# DBS.net
KiCad netlist of a schematic drawn in EAGLE
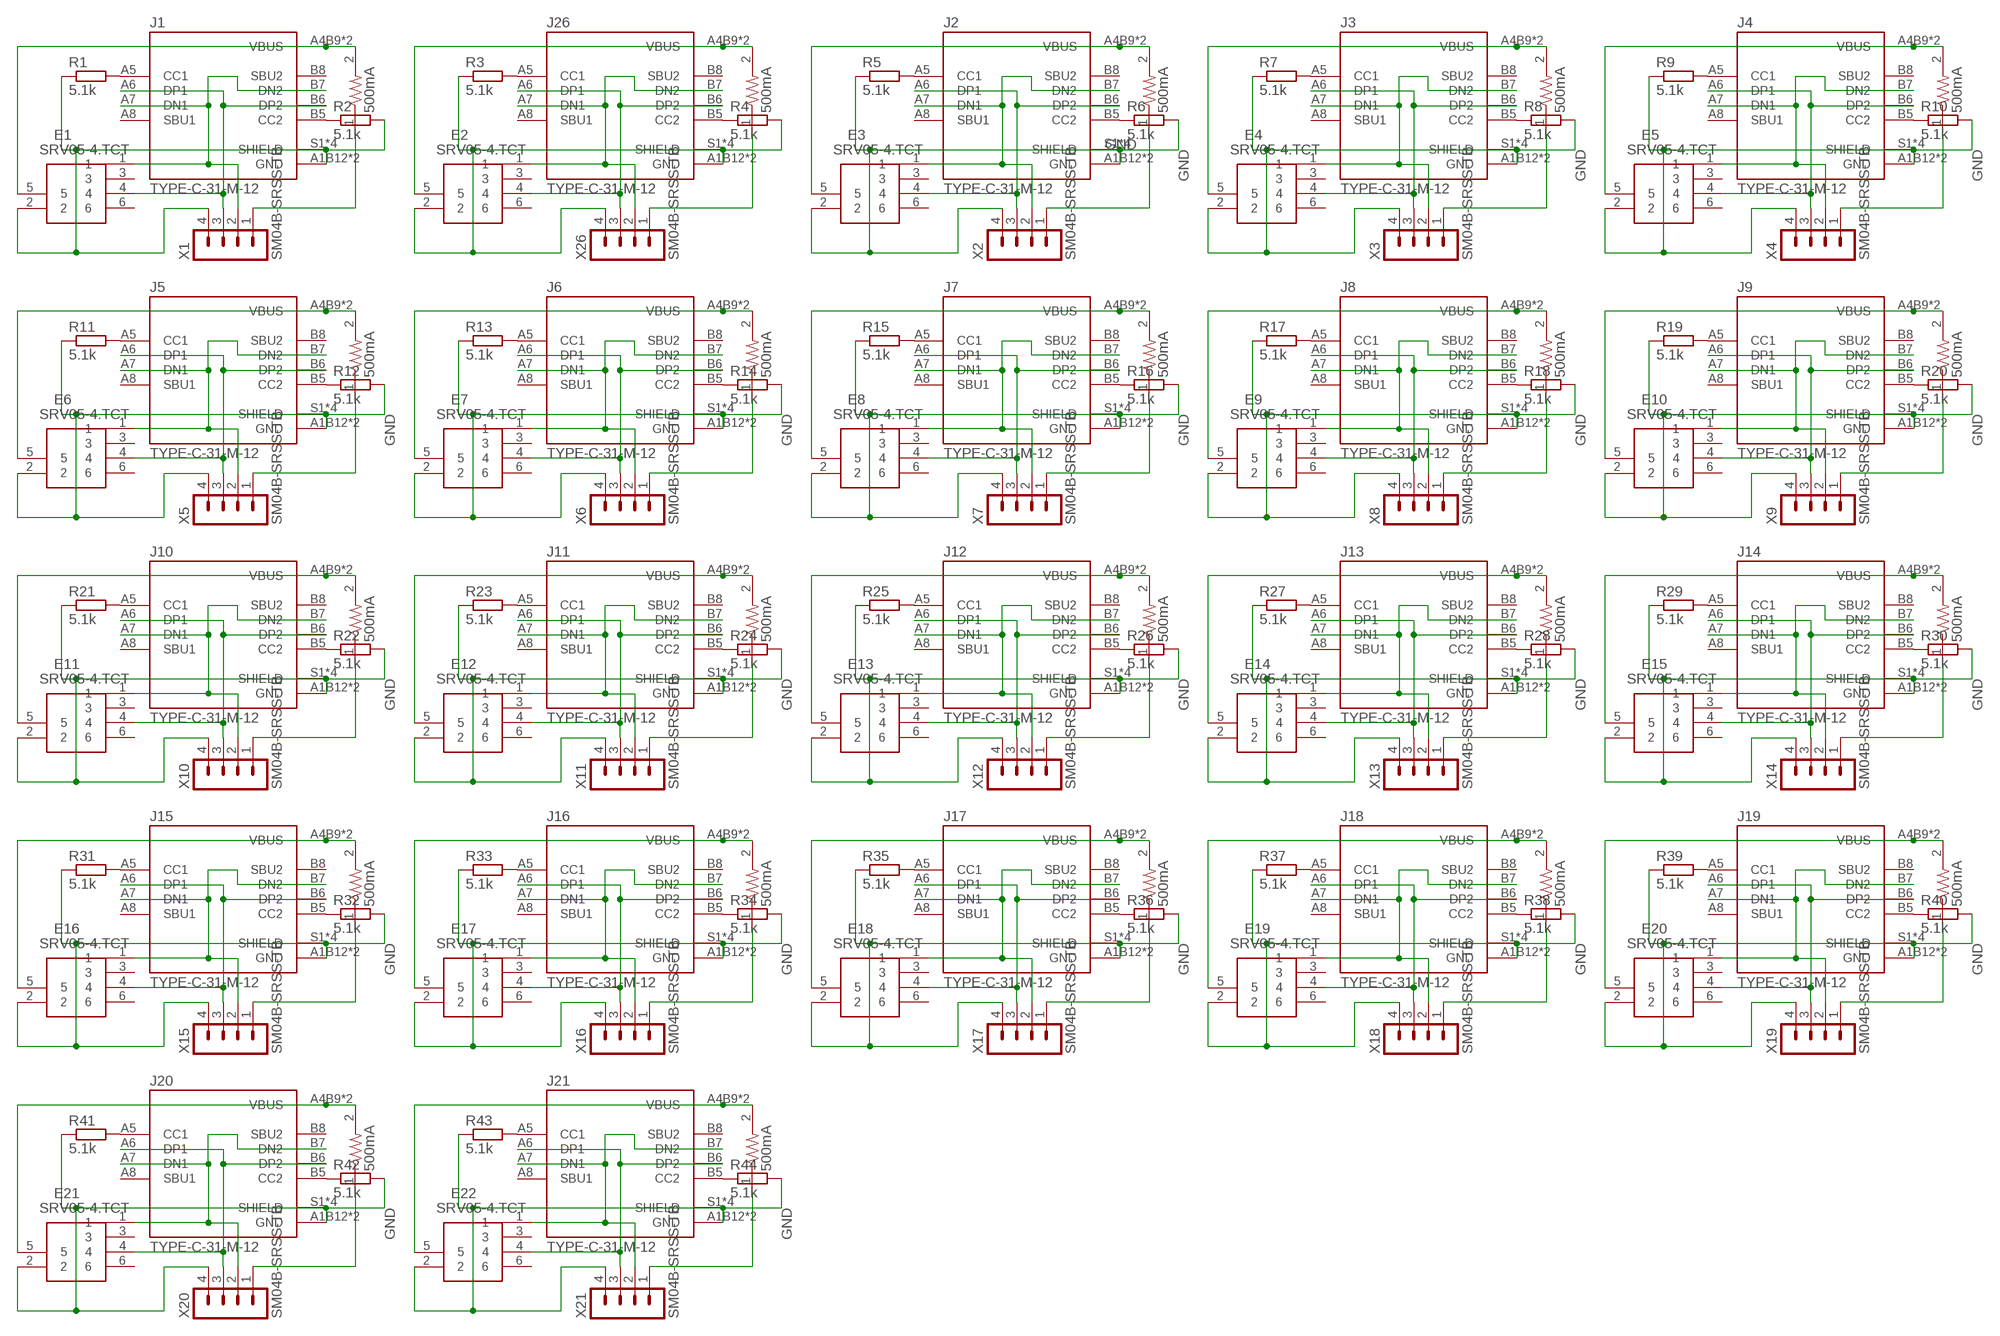
[diagram p0: schematic, sheet 1]

(export (version "E")
  (design (tool "Eeschema 10.0.6"))
  (components
    (comp (ref "E1")
      (value "SRV05-4.TCT")
      (footprint "eagle-import:SOT95P280X145-6N")
      (fields (field (name "MF") "Semtech") (field (name "MP") "SRV05-4.TC"))
      (libsource (lib "eagle-import") (part "SRV05-4.TCT"))
    )
    (comp (ref "E2")
      (value "SRV05-4.TCT")
      (footprint "eagle-import:SOT95P280X145-6N")
      (fields (field (name "MF") "Semtech") (field (name "MP") "SRV05-4.TC"))
      (libsource (lib "eagle-import") (part "SRV05-4.TCT"))
    )
    (comp (ref "E3")
      (value "SRV05-4.TCT")
      (footprint "eagle-import:SOT95P280X145-6N")
      (fields (field (name "MF") "Semtech") (field (name "MP") "SRV05-4.TC"))
      (libsource (lib "eagle-import") (part "SRV05-4.TCT"))
    )
    (comp (ref "E4")
      (value "SRV05-4.TCT")
      (footprint "eagle-import:SOT95P280X145-6N")
      (fields (field (name "MF") "Semtech") (field (name "MP") "SRV05-4.TC"))
      (libsource (lib "eagle-import") (part "SRV05-4.TCT"))
    )
    (comp (ref "E5")
      (value "SRV05-4.TCT")
      (footprint "eagle-import:SOT95P280X145-6N")
      (fields (field (name "MF") "Semtech") (field (name "MP") "SRV05-4.TC"))
      (libsource (lib "eagle-import") (part "SRV05-4.TCT"))
    )
    (comp (ref "E6")
      (value "SRV05-4.TCT")
      (footprint "eagle-import:SOT95P280X145-6N")
      (fields (field (name "MF") "Semtech") (field (name "MP") "SRV05-4.TC"))
      (libsource (lib "eagle-import") (part "SRV05-4.TCT"))
    )
    (comp (ref "E7")
      (value "SRV05-4.TCT")
      (footprint "eagle-import:SOT95P280X145-6N")
      (fields (field (name "MF") "Semtech") (field (name "MP") "SRV05-4.TC"))
      (libsource (lib "eagle-import") (part "SRV05-4.TCT"))
    )
    (comp (ref "E8")
      (value "SRV05-4.TCT")
      (footprint "eagle-import:SOT95P280X145-6N")
      (fields (field (name "MF") "Semtech") (field (name "MP") "SRV05-4.TC"))
      (libsource (lib "eagle-import") (part "SRV05-4.TCT"))
    )
    (comp (ref "E9")
      (value "SRV05-4.TCT")
      (footprint "eagle-import:SOT95P280X145-6N")
      (fields (field (name "MF") "Semtech") (field (name "MP") "SRV05-4.TC"))
      (libsource (lib "eagle-import") (part "SRV05-4.TCT"))
    )
    (comp (ref "E10")
      (value "SRV05-4.TCT")
      (footprint "eagle-import:SOT95P280X145-6N")
      (fields (field (name "MF") "Semtech") (field (name "MP") "SRV05-4.TC"))
      (libsource (lib "eagle-import") (part "SRV05-4.TCT"))
    )
    (comp (ref "E11")
      (value "SRV05-4.TCT")
      (footprint "eagle-import:SOT95P280X145-6N")
      (fields (field (name "MF") "Semtech") (field (name "MP") "SRV05-4.TC"))
      (libsource (lib "eagle-import") (part "SRV05-4.TCT"))
    )
    (comp (ref "E12")
      (value "SRV05-4.TCT")
      (footprint "eagle-import:SOT95P280X145-6N")
      (fields (field (name "MF") "Semtech") (field (name "MP") "SRV05-4.TC"))
      (libsource (lib "eagle-import") (part "SRV05-4.TCT"))
    )
    (comp (ref "E13")
      (value "SRV05-4.TCT")
      (footprint "eagle-import:SOT95P280X145-6N")
      (fields (field (name "MF") "Semtech") (field (name "MP") "SRV05-4.TC"))
      (libsource (lib "eagle-import") (part "SRV05-4.TCT"))
    )
    (comp (ref "E14")
      (value "SRV05-4.TCT")
      (footprint "eagle-import:SOT95P280X145-6N")
      (fields (field (name "MF") "Semtech") (field (name "MP") "SRV05-4.TC"))
      (libsource (lib "eagle-import") (part "SRV05-4.TCT"))
    )
    (comp (ref "E15")
      (value "SRV05-4.TCT")
      (footprint "eagle-import:SOT95P280X145-6N")
      (fields (field (name "MF") "Semtech") (field (name "MP") "SRV05-4.TC"))
      (libsource (lib "eagle-import") (part "SRV05-4.TCT"))
    )
    (comp (ref "E16")
      (value "SRV05-4.TCT")
      (footprint "eagle-import:SOT95P280X145-6N")
      (fields (field (name "MF") "Semtech") (field (name "MP") "SRV05-4.TC"))
      (libsource (lib "eagle-import") (part "SRV05-4.TCT"))
    )
    (comp (ref "E17")
      (value "SRV05-4.TCT")
      (footprint "eagle-import:SOT95P280X145-6N")
      (fields (field (name "MF") "Semtech") (field (name "MP") "SRV05-4.TC"))
      (libsource (lib "eagle-import") (part "SRV05-4.TCT"))
    )
    (comp (ref "E18")
      (value "SRV05-4.TCT")
      (footprint "eagle-import:SOT95P280X145-6N")
      (fields (field (name "MF") "Semtech") (field (name "MP") "SRV05-4.TC"))
      (libsource (lib "eagle-import") (part "SRV05-4.TCT"))
    )
    (comp (ref "E19")
      (value "SRV05-4.TCT")
      (footprint "eagle-import:SOT95P280X145-6N")
      (fields (field (name "MF") "Semtech") (field (name "MP") "SRV05-4.TC"))
      (libsource (lib "eagle-import") (part "SRV05-4.TCT"))
    )
    (comp (ref "E20")
      (value "SRV05-4.TCT")
      (footprint "eagle-import:SOT95P280X145-6N")
      (fields (field (name "MF") "Semtech") (field (name "MP") "SRV05-4.TC"))
      (libsource (lib "eagle-import") (part "SRV05-4.TCT"))
    )
    (comp (ref "E21")
      (value "SRV05-4.TCT")
      (footprint "eagle-import:SOT95P280X145-6N")
      (fields (field (name "MF") "Semtech") (field (name "MP") "SRV05-4.TC"))
      (libsource (lib "eagle-import") (part "SRV05-4.TCT"))
    )
    (comp (ref "E22")
      (value "SRV05-4.TCT")
      (footprint "eagle-import:SOT95P280X145-6N")
      (fields (field (name "MF") "Semtech") (field (name "MP") "SRV05-4.TC"))
      (libsource (lib "eagle-import") (part "SRV05-4.TCT"))
    )
    (comp (ref "F1")
      (value "500mA")
      (footprint "eagle-import:RESC3216X125N")
      (fields (field (name "MF") "Bel Fuse") (field (name "MP") "0ZCJ0075AF2E"))
      (libsource (lib "eagle-import") (part "0ZCJ0075AF2E"))
    )
    (comp (ref "F2")
      (value "500mA")
      (footprint "eagle-import:RESC3216X125N")
      (fields (field (name "MF") "Bel Fuse") (field (name "MP") "0ZCJ0075AF2E"))
      (libsource (lib "eagle-import") (part "0ZCJ0075AF2E"))
    )
    (comp (ref "F3")
      (value "500mA")
      (footprint "eagle-import:RESC3216X125N")
      (fields (field (name "MF") "Bel Fuse") (field (name "MP") "0ZCJ0075AF2E"))
      (libsource (lib "eagle-import") (part "0ZCJ0075AF2E"))
    )
    (comp (ref "F4")
      (value "500mA")
      (footprint "eagle-import:RESC3216X125N")
      (fields (field (name "MF") "Bel Fuse") (field (name "MP") "0ZCJ0075AF2E"))
      (libsource (lib "eagle-import") (part "0ZCJ0075AF2E"))
    )
    (comp (ref "F5")
      (value "500mA")
      (footprint "eagle-import:RESC3216X125N")
      (fields (field (name "MF") "Bel Fuse") (field (name "MP") "0ZCJ0075AF2E"))
      (libsource (lib "eagle-import") (part "0ZCJ0075AF2E"))
    )
    (comp (ref "F6")
      (value "500mA")
      (footprint "eagle-import:RESC3216X125N")
      (fields (field (name "MF") "Bel Fuse") (field (name "MP") "0ZCJ0075AF2E"))
      (libsource (lib "eagle-import") (part "0ZCJ0075AF2E"))
    )
    (comp (ref "F7")
      (value "500mA")
      (footprint "eagle-import:RESC3216X125N")
      (fields (field (name "MF") "Bel Fuse") (field (name "MP") "0ZCJ0075AF2E"))
      (libsource (lib "eagle-import") (part "0ZCJ0075AF2E"))
    )
    (comp (ref "F8")
      (value "500mA")
      (footprint "eagle-import:RESC3216X125N")
      (fields (field (name "MF") "Bel Fuse") (field (name "MP") "0ZCJ0075AF2E"))
      (libsource (lib "eagle-import") (part "0ZCJ0075AF2E"))
    )
    (comp (ref "F9")
      (value "500mA")
      (footprint "eagle-import:RESC3216X125N")
      (fields (field (name "MF") "Bel Fuse") (field (name "MP") "0ZCJ0075AF2E"))
      (libsource (lib "eagle-import") (part "0ZCJ0075AF2E"))
    )
    (comp (ref "F10")
      (value "500mA")
      (footprint "eagle-import:RESC3216X125N")
      (fields (field (name "MF") "Bel Fuse") (field (name "MP") "0ZCJ0075AF2E"))
      (libsource (lib "eagle-import") (part "0ZCJ0075AF2E"))
    )
    (comp (ref "F11")
      (value "500mA")
      (footprint "eagle-import:RESC3216X125N")
      (fields (field (name "MF") "Bel Fuse") (field (name "MP") "0ZCJ0075AF2E"))
      (libsource (lib "eagle-import") (part "0ZCJ0075AF2E"))
    )
    (comp (ref "F12")
      (value "500mA")
      (footprint "eagle-import:RESC3216X125N")
      (fields (field (name "MF") "Bel Fuse") (field (name "MP") "0ZCJ0075AF2E"))
      (libsource (lib "eagle-import") (part "0ZCJ0075AF2E"))
    )
    (comp (ref "F13")
      (value "500mA")
      (footprint "eagle-import:RESC3216X125N")
      (fields (field (name "MF") "Bel Fuse") (field (name "MP") "0ZCJ0075AF2E"))
      (libsource (lib "eagle-import") (part "0ZCJ0075AF2E"))
    )
    (comp (ref "F14")
      (value "500mA")
      (footprint "eagle-import:RESC3216X125N")
      (fields (field (name "MF") "Bel Fuse") (field (name "MP") "0ZCJ0075AF2E"))
      (libsource (lib "eagle-import") (part "0ZCJ0075AF2E"))
    )
    (comp (ref "F15")
      (value "500mA")
      (footprint "eagle-import:RESC3216X125N")
      (fields (field (name "MF") "Bel Fuse") (field (name "MP") "0ZCJ0075AF2E"))
      (libsource (lib "eagle-import") (part "0ZCJ0075AF2E"))
    )
    (comp (ref "F16")
      (value "500mA")
      (footprint "eagle-import:RESC3216X125N")
      (fields (field (name "MF") "Bel Fuse") (field (name "MP") "0ZCJ0075AF2E"))
      (libsource (lib "eagle-import") (part "0ZCJ0075AF2E"))
    )
    (comp (ref "F17")
      (value "500mA")
      (footprint "eagle-import:RESC3216X125N")
      (fields (field (name "MF") "Bel Fuse") (field (name "MP") "0ZCJ0075AF2E"))
      (libsource (lib "eagle-import") (part "0ZCJ0075AF2E"))
    )
    (comp (ref "F18")
      (value "500mA")
      (footprint "eagle-import:RESC3216X125N")
      (fields (field (name "MF") "Bel Fuse") (field (name "MP") "0ZCJ0075AF2E"))
      (libsource (lib "eagle-import") (part "0ZCJ0075AF2E"))
    )
    (comp (ref "F19")
      (value "500mA")
      (footprint "eagle-import:RESC3216X125N")
      (fields (field (name "MF") "Bel Fuse") (field (name "MP") "0ZCJ0075AF2E"))
      (libsource (lib "eagle-import") (part "0ZCJ0075AF2E"))
    )
    (comp (ref "F20")
      (value "500mA")
      (footprint "eagle-import:RESC3216X125N")
      (fields (field (name "MF") "Bel Fuse") (field (name "MP") "0ZCJ0075AF2E"))
      (libsource (lib "eagle-import") (part "0ZCJ0075AF2E"))
    )
    (comp (ref "F21")
      (value "500mA")
      (footprint "eagle-import:RESC3216X125N")
      (fields (field (name "MF") "Bel Fuse") (field (name "MP") "0ZCJ0075AF2E"))
      (libsource (lib "eagle-import") (part "0ZCJ0075AF2E"))
    )
    (comp (ref "F22")
      (value "500mA")
      (footprint "eagle-import:RESC3216X125N")
      (fields (field (name "MF") "Bel Fuse") (field (name "MP") "0ZCJ0075AF2E"))
      (libsource (lib "eagle-import") (part "0ZCJ0075AF2E"))
    )
    (comp (ref "J1")
      (value "TYPE-C-31-M-12")
      (footprint "eagle-import:HRO_TYPE-C-31-M-12")
      (fields (field (name "MF") "HRO Electronics Co., Ltd."))
      (libsource (lib "eagle-import") (part "TYPE-C-31-M-12"))
    )
    (comp (ref "J2")
      (value "TYPE-C-31-M-12")
      (footprint "eagle-import:HRO_TYPE-C-31-M-12")
      (fields (field (name "MF") "HRO Electronics Co., Ltd."))
      (libsource (lib "eagle-import") (part "TYPE-C-31-M-12"))
    )
    (comp (ref "J3")
      (value "TYPE-C-31-M-12")
      (footprint "eagle-import:HRO_TYPE-C-31-M-12")
      (fields (field (name "MF") "HRO Electronics Co., Ltd."))
      (libsource (lib "eagle-import") (part "TYPE-C-31-M-12"))
    )
    (comp (ref "J4")
      (value "TYPE-C-31-M-12")
      (footprint "eagle-import:HRO_TYPE-C-31-M-12")
      (fields (field (name "MF") "HRO Electronics Co., Ltd."))
      (libsource (lib "eagle-import") (part "TYPE-C-31-M-12"))
    )
    (comp (ref "J5")
      (value "TYPE-C-31-M-12")
      (footprint "eagle-import:HRO_TYPE-C-31-M-12")
      (fields (field (name "MF") "HRO Electronics Co., Ltd."))
      (libsource (lib "eagle-import") (part "TYPE-C-31-M-12"))
    )
    (comp (ref "J6")
      (value "TYPE-C-31-M-12")
      (footprint "eagle-import:HRO_TYPE-C-31-M-12")
      (fields (field (name "MF") "HRO Electronics Co., Ltd."))
      (libsource (lib "eagle-import") (part "TYPE-C-31-M-12"))
    )
    (comp (ref "J7")
      (value "TYPE-C-31-M-12")
      (footprint "eagle-import:HRO_TYPE-C-31-M-12")
      (fields (field (name "MF") "HRO Electronics Co., Ltd."))
      (libsource (lib "eagle-import") (part "TYPE-C-31-M-12"))
    )
    (comp (ref "J8")
      (value "TYPE-C-31-M-12")
      (footprint "eagle-import:HRO_TYPE-C-31-M-12")
      (fields (field (name "MF") "HRO Electronics Co., Ltd."))
      (libsource (lib "eagle-import") (part "TYPE-C-31-M-12"))
    )
    (comp (ref "J9")
      (value "TYPE-C-31-M-12")
      (footprint "eagle-import:HRO_TYPE-C-31-M-12")
      (fields (field (name "MF") "HRO Electronics Co., Ltd."))
      (libsource (lib "eagle-import") (part "TYPE-C-31-M-12"))
    )
    (comp (ref "J10")
      (value "TYPE-C-31-M-12")
      (footprint "eagle-import:HRO_TYPE-C-31-M-12")
      (fields (field (name "MF") "HRO Electronics Co., Ltd."))
      (libsource (lib "eagle-import") (part "TYPE-C-31-M-12"))
    )
    (comp (ref "J11")
      (value "TYPE-C-31-M-12")
      (footprint "eagle-import:HRO_TYPE-C-31-M-12")
      (fields (field (name "MF") "HRO Electronics Co., Ltd."))
      (libsource (lib "eagle-import") (part "TYPE-C-31-M-12"))
    )
    (comp (ref "J12")
      (value "TYPE-C-31-M-12")
      (footprint "eagle-import:HRO_TYPE-C-31-M-12")
      (fields (field (name "MF") "HRO Electronics Co., Ltd."))
      (libsource (lib "eagle-import") (part "TYPE-C-31-M-12"))
    )
    (comp (ref "J13")
      (value "TYPE-C-31-M-12")
      (footprint "eagle-import:HRO_TYPE-C-31-M-12")
      (fields (field (name "MF") "HRO Electronics Co., Ltd."))
      (libsource (lib "eagle-import") (part "TYPE-C-31-M-12"))
    )
    (comp (ref "J14")
      (value "TYPE-C-31-M-12")
      (footprint "eagle-import:HRO_TYPE-C-31-M-12")
      (fields (field (name "MF") "HRO Electronics Co., Ltd."))
      (libsource (lib "eagle-import") (part "TYPE-C-31-M-12"))
    )
    (comp (ref "J15")
      (value "TYPE-C-31-M-12")
      (footprint "eagle-import:HRO_TYPE-C-31-M-12")
      (fields (field (name "MF") "HRO Electronics Co., Ltd."))
      (libsource (lib "eagle-import") (part "TYPE-C-31-M-12"))
    )
    (comp (ref "J16")
      (value "TYPE-C-31-M-12")
      (footprint "eagle-import:HRO_TYPE-C-31-M-12")
      (fields (field (name "MF") "HRO Electronics Co., Ltd."))
      (libsource (lib "eagle-import") (part "TYPE-C-31-M-12"))
    )
    (comp (ref "J17")
      (value "TYPE-C-31-M-12")
      (footprint "eagle-import:HRO_TYPE-C-31-M-12")
      (fields (field (name "MF") "HRO Electronics Co., Ltd."))
      (libsource (lib "eagle-import") (part "TYPE-C-31-M-12"))
    )
    (comp (ref "J18")
      (value "TYPE-C-31-M-12")
      (footprint "eagle-import:HRO_TYPE-C-31-M-12")
      (fields (field (name "MF") "HRO Electronics Co., Ltd."))
      (libsource (lib "eagle-import") (part "TYPE-C-31-M-12"))
    )
    (comp (ref "J19")
      (value "TYPE-C-31-M-12")
      (footprint "eagle-import:HRO_TYPE-C-31-M-12")
      (fields (field (name "MF") "HRO Electronics Co., Ltd."))
      (libsource (lib "eagle-import") (part "TYPE-C-31-M-12"))
    )
    (comp (ref "J20")
      (value "TYPE-C-31-M-12")
      (footprint "eagle-import:HRO_TYPE-C-31-M-12")
      (fields (field (name "MF") "HRO Electronics Co., Ltd."))
      (libsource (lib "eagle-import") (part "TYPE-C-31-M-12"))
    )
    (comp (ref "J21")
      (value "TYPE-C-31-M-12")
      (footprint "eagle-import:HRO_TYPE-C-31-M-12")
      (fields (field (name "MF") "HRO Electronics Co., Ltd."))
      (libsource (lib "eagle-import") (part "TYPE-C-31-M-12"))
    )
    (comp (ref "J26")
      (value "TYPE-C-31-M-12")
      (footprint "eagle-import:HRO_TYPE-C-31-M-12")
      (fields (field (name "MF") "HRO Electronics Co., Ltd."))
      (libsource (lib "eagle-import") (part "TYPE-C-31-M-12"))
    )
    (comp (ref "R1")
      (value "5.1k")
      (footprint "eagle-import:R0603")
      (libsource (lib "eagle-import") (part "RESISTOR-0603"))
    )
    (comp (ref "R2")
      (value "5.1k")
      (footprint "eagle-import:R0603")
      (libsource (lib "eagle-import") (part "RESISTOR-0603"))
    )
    (comp (ref "R3")
      (value "5.1k")
      (footprint "eagle-import:R0603")
      (libsource (lib "eagle-import") (part "RESISTOR-0603"))
    )
    (comp (ref "R4")
      (value "5.1k")
      (footprint "eagle-import:R0603")
      (libsource (lib "eagle-import") (part "RESISTOR-0603"))
    )
    (comp (ref "R5")
      (value "5.1k")
      (footprint "eagle-import:R0603")
      (libsource (lib "eagle-import") (part "RESISTOR-0603"))
    )
    (comp (ref "R6")
      (value "5.1k")
      (footprint "eagle-import:R0603")
      (libsource (lib "eagle-import") (part "RESISTOR-0603"))
    )
    (comp (ref "R7")
      (value "5.1k")
      (footprint "eagle-import:R0603")
      (libsource (lib "eagle-import") (part "RESISTOR-0603"))
    )
    (comp (ref "R8")
      (value "5.1k")
      (footprint "eagle-import:R0603")
      (libsource (lib "eagle-import") (part "RESISTOR-0603"))
    )
    (comp (ref "R9")
      (value "5.1k")
      (footprint "eagle-import:R0603")
      (libsource (lib "eagle-import") (part "RESISTOR-0603"))
    )
    (comp (ref "R10")
      (value "5.1k")
      (footprint "eagle-import:R0603")
      (libsource (lib "eagle-import") (part "RESISTOR-0603"))
    )
    (comp (ref "R11")
      (value "5.1k")
      (footprint "eagle-import:R0603")
      (libsource (lib "eagle-import") (part "RESISTOR-0603"))
    )
    (comp (ref "R12")
      (value "5.1k")
      (footprint "eagle-import:R0603")
      (libsource (lib "eagle-import") (part "RESISTOR-0603"))
    )
    (comp (ref "R13")
      (value "5.1k")
      (footprint "eagle-import:R0603")
      (libsource (lib "eagle-import") (part "RESISTOR-0603"))
    )
    (comp (ref "R14")
      (value "5.1k")
      (footprint "eagle-import:R0603")
      (libsource (lib "eagle-import") (part "RESISTOR-0603"))
    )
    (comp (ref "R15")
      (value "5.1k")
      (footprint "eagle-import:R0603")
      (libsource (lib "eagle-import") (part "RESISTOR-0603"))
    )
    (comp (ref "R16")
      (value "5.1k")
      (footprint "eagle-import:R0603")
      (libsource (lib "eagle-import") (part "RESISTOR-0603"))
    )
    (comp (ref "R17")
      (value "5.1k")
      (footprint "eagle-import:R0603")
      (libsource (lib "eagle-import") (part "RESISTOR-0603"))
    )
    (comp (ref "R18")
      (value "5.1k")
      (footprint "eagle-import:R0603")
      (libsource (lib "eagle-import") (part "RESISTOR-0603"))
    )
    (comp (ref "R19")
      (value "5.1k")
      (footprint "eagle-import:R0603")
      (libsource (lib "eagle-import") (part "RESISTOR-0603"))
    )
    (comp (ref "R20")
      (value "5.1k")
      (footprint "eagle-import:R0603")
      (libsource (lib "eagle-import") (part "RESISTOR-0603"))
    )
    (comp (ref "R21")
      (value "5.1k")
      (footprint "eagle-import:R0603")
      (libsource (lib "eagle-import") (part "RESISTOR-0603"))
    )
    (comp (ref "R22")
      (value "5.1k")
      (footprint "eagle-import:R0603")
      (libsource (lib "eagle-import") (part "RESISTOR-0603"))
    )
    (comp (ref "R23")
      (value "5.1k")
      (footprint "eagle-import:R0603")
      (libsource (lib "eagle-import") (part "RESISTOR-0603"))
    )
    (comp (ref "R24")
      (value "5.1k")
      (footprint "eagle-import:R0603")
      (libsource (lib "eagle-import") (part "RESISTOR-0603"))
    )
    (comp (ref "R25")
      (value "5.1k")
      (footprint "eagle-import:R0603")
      (libsource (lib "eagle-import") (part "RESISTOR-0603"))
    )
    (comp (ref "R26")
      (value "5.1k")
      (footprint "eagle-import:R0603")
      (libsource (lib "eagle-import") (part "RESISTOR-0603"))
    )
    (comp (ref "R27")
      (value "5.1k")
      (footprint "eagle-import:R0603")
      (libsource (lib "eagle-import") (part "RESISTOR-0603"))
    )
    (comp (ref "R28")
      (value "5.1k")
      (footprint "eagle-import:R0603")
      (libsource (lib "eagle-import") (part "RESISTOR-0603"))
    )
    (comp (ref "R29")
      (value "5.1k")
      (footprint "eagle-import:R0603")
      (libsource (lib "eagle-import") (part "RESISTOR-0603"))
    )
    (comp (ref "R30")
      (value "5.1k")
      (footprint "eagle-import:R0603")
      (libsource (lib "eagle-import") (part "RESISTOR-0603"))
    )
    (comp (ref "R31")
      (value "5.1k")
      (footprint "eagle-import:R0603")
      (libsource (lib "eagle-import") (part "RESISTOR-0603"))
    )
    (comp (ref "R32")
      (value "5.1k")
      (footprint "eagle-import:R0603")
      (libsource (lib "eagle-import") (part "RESISTOR-0603"))
    )
    (comp (ref "R33")
      (value "5.1k")
      (footprint "eagle-import:R0603")
      (libsource (lib "eagle-import") (part "RESISTOR-0603"))
    )
    (comp (ref "R34")
      (value "5.1k")
      (footprint "eagle-import:R0603")
      (libsource (lib "eagle-import") (part "RESISTOR-0603"))
    )
    (comp (ref "R35")
      (value "5.1k")
      (footprint "eagle-import:R0603")
      (libsource (lib "eagle-import") (part "RESISTOR-0603"))
    )
    (comp (ref "R36")
      (value "5.1k")
      (footprint "eagle-import:R0603")
      (libsource (lib "eagle-import") (part "RESISTOR-0603"))
    )
    (comp (ref "R37")
      (value "5.1k")
      (footprint "eagle-import:R0603")
      (libsource (lib "eagle-import") (part "RESISTOR-0603"))
    )
    (comp (ref "R38")
      (value "5.1k")
      (footprint "eagle-import:R0603")
      (libsource (lib "eagle-import") (part "RESISTOR-0603"))
    )
    (comp (ref "R39")
      (value "5.1k")
      (footprint "eagle-import:R0603")
      (libsource (lib "eagle-import") (part "RESISTOR-0603"))
    )
    (comp (ref "R40")
      (value "5.1k")
      (footprint "eagle-import:R0603")
      (libsource (lib "eagle-import") (part "RESISTOR-0603"))
    )
    (comp (ref "R41")
      (value "5.1k")
      (footprint "eagle-import:R0603")
      (libsource (lib "eagle-import") (part "RESISTOR-0603"))
    )
    (comp (ref "R42")
      (value "5.1k")
      (footprint "eagle-import:R0603")
      (libsource (lib "eagle-import") (part "RESISTOR-0603"))
    )
    (comp (ref "R43")
      (value "5.1k")
      (footprint "eagle-import:R0603")
      (libsource (lib "eagle-import") (part "RESISTOR-0603"))
    )
    (comp (ref "R44")
      (value "5.1k")
      (footprint "eagle-import:R0603")
      (libsource (lib "eagle-import") (part "RESISTOR-0603"))
    )
    (comp (ref "X1")
      (value "SM04B-SRSS-TB")
      (footprint "eagle-import:SM04B-SRSS-TB")
      (libsource (lib "eagle-import") (part "SM04B-SRSS-TB"))
    )
    (comp (ref "X2")
      (value "SM04B-SRSS-TB")
      (footprint "eagle-import:SM04B-SRSS-TB")
      (libsource (lib "eagle-import") (part "SM04B-SRSS-TB"))
    )
    (comp (ref "X3")
      (value "SM04B-SRSS-TB")
      (footprint "eagle-import:SM04B-SRSS-TB")
      (libsource (lib "eagle-import") (part "SM04B-SRSS-TB"))
    )
    (comp (ref "X4")
      (value "SM04B-SRSS-TB")
      (footprint "eagle-import:SM04B-SRSS-TB")
      (libsource (lib "eagle-import") (part "SM04B-SRSS-TB"))
    )
    (comp (ref "X5")
      (value "SM04B-SRSS-TB")
      (footprint "eagle-import:SM04B-SRSS-TB")
      (libsource (lib "eagle-import") (part "SM04B-SRSS-TB"))
    )
    (comp (ref "X6")
      (value "SM04B-SRSS-TB")
      (footprint "eagle-import:SM04B-SRSS-TB")
      (libsource (lib "eagle-import") (part "SM04B-SRSS-TB"))
    )
    (comp (ref "X7")
      (value "SM04B-SRSS-TB")
      (footprint "eagle-import:SM04B-SRSS-TB")
      (libsource (lib "eagle-import") (part "SM04B-SRSS-TB"))
    )
    (comp (ref "X8")
      (value "SM04B-SRSS-TB")
      (footprint "eagle-import:SM04B-SRSS-TB")
      (libsource (lib "eagle-import") (part "SM04B-SRSS-TB"))
    )
    (comp (ref "X9")
      (value "SM04B-SRSS-TB")
      (footprint "eagle-import:SM04B-SRSS-TB")
      (libsource (lib "eagle-import") (part "SM04B-SRSS-TB"))
    )
    (comp (ref "X10")
      (value "SM04B-SRSS-TB")
      (footprint "eagle-import:SM04B-SRSS-TB")
      (libsource (lib "eagle-import") (part "SM04B-SRSS-TB"))
    )
    (comp (ref "X11")
      (value "SM04B-SRSS-TB")
      (footprint "eagle-import:SM04B-SRSS-TB")
      (libsource (lib "eagle-import") (part "SM04B-SRSS-TB"))
    )
    (comp (ref "X12")
      (value "SM04B-SRSS-TB")
      (footprint "eagle-import:SM04B-SRSS-TB")
      (libsource (lib "eagle-import") (part "SM04B-SRSS-TB"))
    )
    (comp (ref "X13")
      (value "SM04B-SRSS-TB")
      (footprint "eagle-import:SM04B-SRSS-TB")
      (libsource (lib "eagle-import") (part "SM04B-SRSS-TB"))
    )
    (comp (ref "X14")
      (value "SM04B-SRSS-TB")
      (footprint "eagle-import:SM04B-SRSS-TB")
      (libsource (lib "eagle-import") (part "SM04B-SRSS-TB"))
    )
    (comp (ref "X15")
      (value "SM04B-SRSS-TB")
      (footprint "eagle-import:SM04B-SRSS-TB")
      (libsource (lib "eagle-import") (part "SM04B-SRSS-TB"))
    )
    (comp (ref "X16")
      (value "SM04B-SRSS-TB")
      (footprint "eagle-import:SM04B-SRSS-TB")
      (libsource (lib "eagle-import") (part "SM04B-SRSS-TB"))
    )
    (comp (ref "X17")
      (value "SM04B-SRSS-TB")
      (footprint "eagle-import:SM04B-SRSS-TB")
      (libsource (lib "eagle-import") (part "SM04B-SRSS-TB"))
    )
    (comp (ref "X18")
      (value "SM04B-SRSS-TB")
      (footprint "eagle-import:SM04B-SRSS-TB")
      (libsource (lib "eagle-import") (part "SM04B-SRSS-TB"))
    )
    (comp (ref "X19")
      (value "SM04B-SRSS-TB")
      (footprint "eagle-import:SM04B-SRSS-TB")
      (libsource (lib "eagle-import") (part "SM04B-SRSS-TB"))
    )
    (comp (ref "X20")
      (value "SM04B-SRSS-TB")
      (footprint "eagle-import:SM04B-SRSS-TB")
      (libsource (lib "eagle-import") (part "SM04B-SRSS-TB"))
    )
    (comp (ref "X21")
      (value "SM04B-SRSS-TB")
      (footprint "eagle-import:SM04B-SRSS-TB")
      (libsource (lib "eagle-import") (part "SM04B-SRSS-TB"))
    )
    (comp (ref "X26")
      (value "SM04B-SRSS-TB")
      (footprint "eagle-import:SM04B-SRSS-TB")
      (libsource (lib "eagle-import") (part "SM04B-SRSS-TB"))
    )
  )
  (nets
    (net (code "1") (name "/GND") (class "Default")
      (node (ref "E1") (pin "2") (pinfunction "2_2") (pintype "bidirectional"))
      (node (ref "E10") (pin "2") (pinfunction "2_2") (pintype "bidirectional"))
      (node (ref "E11") (pin "2") (pinfunction "2_2") (pintype "bidirectional"))
      (node (ref "E12") (pin "2") (pinfunction "2_2") (pintype "bidirectional"))
      (node (ref "E13") (pin "2") (pinfunction "2_2") (pintype "bidirectional"))
      (node (ref "E14") (pin "2") (pinfunction "2_2") (pintype "bidirectional"))
      (node (ref "E15") (pin "2") (pinfunction "2_2") (pintype "bidirectional"))
      (node (ref "E16") (pin "2") (pinfunction "2_2") (pintype "bidirectional"))
      (node (ref "E17") (pin "2") (pinfunction "2_2") (pintype "bidirectional"))
      (node (ref "E18") (pin "2") (pinfunction "2_2") (pintype "bidirectional"))
      (node (ref "E19") (pin "2") (pinfunction "2_2") (pintype "bidirectional"))
      (node (ref "E2") (pin "2") (pinfunction "2_2") (pintype "bidirectional"))
      (node (ref "E20") (pin "2") (pinfunction "2_2") (pintype "bidirectional"))
      (node (ref "E21") (pin "2") (pinfunction "2_2") (pintype "bidirectional"))
      (node (ref "E22") (pin "2") (pinfunction "2_2") (pintype "bidirectional"))
      (node (ref "E3") (pin "2") (pinfunction "2_2") (pintype "bidirectional"))
      (node (ref "E4") (pin "2") (pinfunction "2_2") (pintype "bidirectional"))
      (node (ref "E5") (pin "2") (pinfunction "2_2") (pintype "bidirectional"))
      (node (ref "E6") (pin "2") (pinfunction "2_2") (pintype "bidirectional"))
      (node (ref "E7") (pin "2") (pinfunction "2_2") (pintype "bidirectional"))
      (node (ref "E8") (pin "2") (pinfunction "2_2") (pintype "bidirectional"))
      (node (ref "E9") (pin "2") (pinfunction "2_2") (pintype "bidirectional"))
      (node (ref "J1") (pin "A1B12") (pinfunction "GND_A1B12") (pintype "power_in"))
      (node (ref "J1") (pin "B1A12") (pinfunction "GND_B1A12") (pintype "power_in"))
      (node (ref "J1") (pin "S1") (pinfunction "SHIELD_S1") (pintype "passive"))
      (node (ref "J1") (pin "S2") (pinfunction "SHIELD_S2") (pintype "passive"))
      (node (ref "J1") (pin "S3") (pinfunction "SHIELD_S3") (pintype "passive"))
      (node (ref "J1") (pin "S4") (pinfunction "SHIELD_S4") (pintype "passive"))
      (node (ref "J10") (pin "A1B12") (pinfunction "GND_A1B12") (pintype "power_in"))
      (node (ref "J10") (pin "B1A12") (pinfunction "GND_B1A12") (pintype "power_in"))
      (node (ref "J10") (pin "S1") (pinfunction "SHIELD_S1") (pintype "passive"))
      (node (ref "J10") (pin "S2") (pinfunction "SHIELD_S2") (pintype "passive"))
      (node (ref "J10") (pin "S3") (pinfunction "SHIELD_S3") (pintype "passive"))
      (node (ref "J10") (pin "S4") (pinfunction "SHIELD_S4") (pintype "passive"))
      (node (ref "J11") (pin "A1B12") (pinfunction "GND_A1B12") (pintype "power_in"))
      (node (ref "J11") (pin "B1A12") (pinfunction "GND_B1A12") (pintype "power_in"))
      (node (ref "J11") (pin "S1") (pinfunction "SHIELD_S1") (pintype "passive"))
      (node (ref "J11") (pin "S2") (pinfunction "SHIELD_S2") (pintype "passive"))
      (node (ref "J11") (pin "S3") (pinfunction "SHIELD_S3") (pintype "passive"))
      (node (ref "J11") (pin "S4") (pinfunction "SHIELD_S4") (pintype "passive"))
      (node (ref "J12") (pin "A1B12") (pinfunction "GND_A1B12") (pintype "power_in"))
      (node (ref "J12") (pin "B1A12") (pinfunction "GND_B1A12") (pintype "power_in"))
      (node (ref "J12") (pin "S1") (pinfunction "SHIELD_S1") (pintype "passive"))
      (node (ref "J12") (pin "S2") (pinfunction "SHIELD_S2") (pintype "passive"))
      (node (ref "J12") (pin "S3") (pinfunction "SHIELD_S3") (pintype "passive"))
      (node (ref "J12") (pin "S4") (pinfunction "SHIELD_S4") (pintype "passive"))
      (node (ref "J13") (pin "A1B12") (pinfunction "GND_A1B12") (pintype "power_in"))
      (node (ref "J13") (pin "B1A12") (pinfunction "GND_B1A12") (pintype "power_in"))
      (node (ref "J13") (pin "S1") (pinfunction "SHIELD_S1") (pintype "passive"))
      (node (ref "J13") (pin "S2") (pinfunction "SHIELD_S2") (pintype "passive"))
      (node (ref "J13") (pin "S3") (pinfunction "SHIELD_S3") (pintype "passive"))
      (node (ref "J13") (pin "S4") (pinfunction "SHIELD_S4") (pintype "passive"))
      (node (ref "J14") (pin "A1B12") (pinfunction "GND_A1B12") (pintype "power_in"))
      (node (ref "J14") (pin "B1A12") (pinfunction "GND_B1A12") (pintype "power_in"))
      (node (ref "J14") (pin "S1") (pinfunction "SHIELD_S1") (pintype "passive"))
      (node (ref "J14") (pin "S2") (pinfunction "SHIELD_S2") (pintype "passive"))
      (node (ref "J14") (pin "S3") (pinfunction "SHIELD_S3") (pintype "passive"))
      (node (ref "J14") (pin "S4") (pinfunction "SHIELD_S4") (pintype "passive"))
      (node (ref "J15") (pin "A1B12") (pinfunction "GND_A1B12") (pintype "power_in"))
      (node (ref "J15") (pin "B1A12") (pinfunction "GND_B1A12") (pintype "power_in"))
      (node (ref "J15") (pin "S1") (pinfunction "SHIELD_S1") (pintype "passive"))
      (node (ref "J15") (pin "S2") (pinfunction "SHIELD_S2") (pintype "passive"))
      (node (ref "J15") (pin "S3") (pinfunction "SHIELD_S3") (pintype "passive"))
      (node (ref "J15") (pin "S4") (pinfunction "SHIELD_S4") (pintype "passive"))
      (node (ref "J16") (pin "A1B12") (pinfunction "GND_A1B12") (pintype "power_in"))
      (node (ref "J16") (pin "B1A12") (pinfunction "GND_B1A12") (pintype "power_in"))
      (node (ref "J16") (pin "S1") (pinfunction "SHIELD_S1") (pintype "passive"))
      (node (ref "J16") (pin "S2") (pinfunction "SHIELD_S2") (pintype "passive"))
      (node (ref "J16") (pin "S3") (pinfunction "SHIELD_S3") (pintype "passive"))
      (node (ref "J16") (pin "S4") (pinfunction "SHIELD_S4") (pintype "passive"))
      (node (ref "J17") (pin "A1B12") (pinfunction "GND_A1B12") (pintype "power_in"))
      (node (ref "J17") (pin "B1A12") (pinfunction "GND_B1A12") (pintype "power_in"))
      (node (ref "J17") (pin "S1") (pinfunction "SHIELD_S1") (pintype "passive"))
      (node (ref "J17") (pin "S2") (pinfunction "SHIELD_S2") (pintype "passive"))
      (node (ref "J17") (pin "S3") (pinfunction "SHIELD_S3") (pintype "passive"))
      (node (ref "J17") (pin "S4") (pinfunction "SHIELD_S4") (pintype "passive"))
      (node (ref "J18") (pin "A1B12") (pinfunction "GND_A1B12") (pintype "power_in"))
      (node (ref "J18") (pin "B1A12") (pinfunction "GND_B1A12") (pintype "power_in"))
      (node (ref "J18") (pin "S1") (pinfunction "SHIELD_S1") (pintype "passive"))
      (node (ref "J18") (pin "S2") (pinfunction "SHIELD_S2") (pintype "passive"))
      (node (ref "J18") (pin "S3") (pinfunction "SHIELD_S3") (pintype "passive"))
      (node (ref "J18") (pin "S4") (pinfunction "SHIELD_S4") (pintype "passive"))
      (node (ref "J19") (pin "A1B12") (pinfunction "GND_A1B12") (pintype "power_in"))
      (node (ref "J19") (pin "B1A12") (pinfunction "GND_B1A12") (pintype "power_in"))
      (node (ref "J19") (pin "S1") (pinfunction "SHIELD_S1") (pintype "passive"))
      (node (ref "J19") (pin "S2") (pinfunction "SHIELD_S2") (pintype "passive"))
      (node (ref "J19") (pin "S3") (pinfunction "SHIELD_S3") (pintype "passive"))
      (node (ref "J19") (pin "S4") (pinfunction "SHIELD_S4") (pintype "passive"))
      (node (ref "J2") (pin "A1B12") (pinfunction "GND_A1B12") (pintype "power_in"))
      (node (ref "J2") (pin "B1A12") (pinfunction "GND_B1A12") (pintype "power_in"))
      (node (ref "J2") (pin "S1") (pinfunction "SHIELD_S1") (pintype "passive"))
      (node (ref "J2") (pin "S2") (pinfunction "SHIELD_S2") (pintype "passive"))
      (node (ref "J2") (pin "S3") (pinfunction "SHIELD_S3") (pintype "passive"))
      (node (ref "J2") (pin "S4") (pinfunction "SHIELD_S4") (pintype "passive"))
      (node (ref "J20") (pin "A1B12") (pinfunction "GND_A1B12") (pintype "power_in"))
      (node (ref "J20") (pin "B1A12") (pinfunction "GND_B1A12") (pintype "power_in"))
      (node (ref "J20") (pin "S1") (pinfunction "SHIELD_S1") (pintype "passive"))
      (node (ref "J20") (pin "S2") (pinfunction "SHIELD_S2") (pintype "passive"))
      (node (ref "J20") (pin "S3") (pinfunction "SHIELD_S3") (pintype "passive"))
      (node (ref "J20") (pin "S4") (pinfunction "SHIELD_S4") (pintype "passive"))
      (node (ref "J21") (pin "A1B12") (pinfunction "GND_A1B12") (pintype "power_in"))
      (node (ref "J21") (pin "B1A12") (pinfunction "GND_B1A12") (pintype "power_in"))
      (node (ref "J21") (pin "S1") (pinfunction "SHIELD_S1") (pintype "passive"))
      (node (ref "J21") (pin "S2") (pinfunction "SHIELD_S2") (pintype "passive"))
      (node (ref "J21") (pin "S3") (pinfunction "SHIELD_S3") (pintype "passive"))
      (node (ref "J21") (pin "S4") (pinfunction "SHIELD_S4") (pintype "passive"))
      (node (ref "J26") (pin "A1B12") (pinfunction "GND_A1B12") (pintype "power_in"))
      (node (ref "J26") (pin "B1A12") (pinfunction "GND_B1A12") (pintype "power_in"))
      (node (ref "J26") (pin "S1") (pinfunction "SHIELD_S1") (pintype "passive"))
      (node (ref "J26") (pin "S2") (pinfunction "SHIELD_S2") (pintype "passive"))
      (node (ref "J26") (pin "S3") (pinfunction "SHIELD_S3") (pintype "passive"))
      (node (ref "J26") (pin "S4") (pinfunction "SHIELD_S4") (pintype "passive"))
      (node (ref "J3") (pin "A1B12") (pinfunction "GND_A1B12") (pintype "power_in"))
      (node (ref "J3") (pin "B1A12") (pinfunction "GND_B1A12") (pintype "power_in"))
      (node (ref "J3") (pin "S1") (pinfunction "SHIELD_S1") (pintype "passive"))
      (node (ref "J3") (pin "S2") (pinfunction "SHIELD_S2") (pintype "passive"))
      (node (ref "J3") (pin "S3") (pinfunction "SHIELD_S3") (pintype "passive"))
      (node (ref "J3") (pin "S4") (pinfunction "SHIELD_S4") (pintype "passive"))
      (node (ref "J4") (pin "A1B12") (pinfunction "GND_A1B12") (pintype "power_in"))
      (node (ref "J4") (pin "B1A12") (pinfunction "GND_B1A12") (pintype "power_in"))
      (node (ref "J4") (pin "S1") (pinfunction "SHIELD_S1") (pintype "passive"))
      (node (ref "J4") (pin "S2") (pinfunction "SHIELD_S2") (pintype "passive"))
      (node (ref "J4") (pin "S3") (pinfunction "SHIELD_S3") (pintype "passive"))
      (node (ref "J4") (pin "S4") (pinfunction "SHIELD_S4") (pintype "passive"))
      (node (ref "J5") (pin "A1B12") (pinfunction "GND_A1B12") (pintype "power_in"))
      (node (ref "J5") (pin "B1A12") (pinfunction "GND_B1A12") (pintype "power_in"))
      (node (ref "J5") (pin "S1") (pinfunction "SHIELD_S1") (pintype "passive"))
      (node (ref "J5") (pin "S2") (pinfunction "SHIELD_S2") (pintype "passive"))
      (node (ref "J5") (pin "S3") (pinfunction "SHIELD_S3") (pintype "passive"))
      (node (ref "J5") (pin "S4") (pinfunction "SHIELD_S4") (pintype "passive"))
      (node (ref "J6") (pin "A1B12") (pinfunction "GND_A1B12") (pintype "power_in"))
      (node (ref "J6") (pin "B1A12") (pinfunction "GND_B1A12") (pintype "power_in"))
      (node (ref "J6") (pin "S1") (pinfunction "SHIELD_S1") (pintype "passive"))
      (node (ref "J6") (pin "S2") (pinfunction "SHIELD_S2") (pintype "passive"))
      (node (ref "J6") (pin "S3") (pinfunction "SHIELD_S3") (pintype "passive"))
      (node (ref "J6") (pin "S4") (pinfunction "SHIELD_S4") (pintype "passive"))
      (node (ref "J7") (pin "A1B12") (pinfunction "GND_A1B12") (pintype "power_in"))
      (node (ref "J7") (pin "B1A12") (pinfunction "GND_B1A12") (pintype "power_in"))
      (node (ref "J7") (pin "S1") (pinfunction "SHIELD_S1") (pintype "passive"))
      (node (ref "J7") (pin "S2") (pinfunction "SHIELD_S2") (pintype "passive"))
      (node (ref "J7") (pin "S3") (pinfunction "SHIELD_S3") (pintype "passive"))
      (node (ref "J7") (pin "S4") (pinfunction "SHIELD_S4") (pintype "passive"))
      (node (ref "J8") (pin "A1B12") (pinfunction "GND_A1B12") (pintype "power_in"))
      (node (ref "J8") (pin "B1A12") (pinfunction "GND_B1A12") (pintype "power_in"))
      (node (ref "J8") (pin "S1") (pinfunction "SHIELD_S1") (pintype "passive"))
      (node (ref "J8") (pin "S2") (pinfunction "SHIELD_S2") (pintype "passive"))
      (node (ref "J8") (pin "S3") (pinfunction "SHIELD_S3") (pintype "passive"))
      (node (ref "J8") (pin "S4") (pinfunction "SHIELD_S4") (pintype "passive"))
      (node (ref "J9") (pin "A1B12") (pinfunction "GND_A1B12") (pintype "power_in"))
      (node (ref "J9") (pin "B1A12") (pinfunction "GND_B1A12") (pintype "power_in"))
      (node (ref "J9") (pin "S1") (pinfunction "SHIELD_S1") (pintype "passive"))
      (node (ref "J9") (pin "S2") (pinfunction "SHIELD_S2") (pintype "passive"))
      (node (ref "J9") (pin "S3") (pinfunction "SHIELD_S3") (pintype "passive"))
      (node (ref "J9") (pin "S4") (pinfunction "SHIELD_S4") (pintype "passive"))
      (node (ref "R1") (pin "1") (pinfunction "1_1") (pintype "passive"))
      (node (ref "R10") (pin "2") (pinfunction "2_2") (pintype "passive"))
      (node (ref "R11") (pin "1") (pinfunction "1_1") (pintype "passive"))
      (node (ref "R12") (pin "2") (pinfunction "2_2") (pintype "passive"))
      (node (ref "R13") (pin "1") (pinfunction "1_1") (pintype "passive"))
      (node (ref "R14") (pin "2") (pinfunction "2_2") (pintype "passive"))
      (node (ref "R15") (pin "1") (pinfunction "1_1") (pintype "passive"))
      (node (ref "R16") (pin "2") (pinfunction "2_2") (pintype "passive"))
      (node (ref "R17") (pin "1") (pinfunction "1_1") (pintype "passive"))
      (node (ref "R18") (pin "2") (pinfunction "2_2") (pintype "passive"))
      (node (ref "R19") (pin "1") (pinfunction "1_1") (pintype "passive"))
      (node (ref "R2") (pin "2") (pinfunction "2_2") (pintype "passive"))
      (node (ref "R20") (pin "2") (pinfunction "2_2") (pintype "passive"))
      (node (ref "R21") (pin "1") (pinfunction "1_1") (pintype "passive"))
      (node (ref "R22") (pin "2") (pinfunction "2_2") (pintype "passive"))
      (node (ref "R23") (pin "1") (pinfunction "1_1") (pintype "passive"))
      (node (ref "R24") (pin "2") (pinfunction "2_2") (pintype "passive"))
      (node (ref "R25") (pin "1") (pinfunction "1_1") (pintype "passive"))
      (node (ref "R26") (pin "2") (pinfunction "2_2") (pintype "passive"))
      (node (ref "R27") (pin "1") (pinfunction "1_1") (pintype "passive"))
      (node (ref "R28") (pin "2") (pinfunction "2_2") (pintype "passive"))
      (node (ref "R29") (pin "1") (pinfunction "1_1") (pintype "passive"))
      (node (ref "R3") (pin "1") (pinfunction "1_1") (pintype "passive"))
      (node (ref "R30") (pin "2") (pinfunction "2_2") (pintype "passive"))
      (node (ref "R31") (pin "1") (pinfunction "1_1") (pintype "passive"))
      (node (ref "R32") (pin "2") (pinfunction "2_2") (pintype "passive"))
      (node (ref "R33") (pin "1") (pinfunction "1_1") (pintype "passive"))
      (node (ref "R34") (pin "2") (pinfunction "2_2") (pintype "passive"))
      (node (ref "R35") (pin "1") (pinfunction "1_1") (pintype "passive"))
      (node (ref "R36") (pin "2") (pinfunction "2_2") (pintype "passive"))
      (node (ref "R37") (pin "1") (pinfunction "1_1") (pintype "passive"))
      (node (ref "R38") (pin "2") (pinfunction "2_2") (pintype "passive"))
      (node (ref "R39") (pin "1") (pinfunction "1_1") (pintype "passive"))
      (node (ref "R4") (pin "2") (pinfunction "2_2") (pintype "passive"))
      (node (ref "R40") (pin "2") (pinfunction "2_2") (pintype "passive"))
      (node (ref "R41") (pin "1") (pinfunction "1_1") (pintype "passive"))
      (node (ref "R42") (pin "2") (pinfunction "2_2") (pintype "passive"))
      (node (ref "R43") (pin "1") (pinfunction "1_1") (pintype "passive"))
      (node (ref "R44") (pin "2") (pinfunction "2_2") (pintype "passive"))
      (node (ref "R5") (pin "1") (pinfunction "1_1") (pintype "passive"))
      (node (ref "R6") (pin "2") (pinfunction "2_2") (pintype "passive"))
      (node (ref "R7") (pin "1") (pinfunction "1_1") (pintype "passive"))
      (node (ref "R8") (pin "2") (pinfunction "2_2") (pintype "passive"))
      (node (ref "R9") (pin "1") (pinfunction "1_1") (pintype "passive"))
      (node (ref "X1") (pin "4") (pinfunction "4_4") (pintype "passive"))
      (node (ref "X10") (pin "4") (pinfunction "4_4") (pintype "passive"))
      (node (ref "X11") (pin "4") (pinfunction "4_4") (pintype "passive"))
      (node (ref "X12") (pin "4") (pinfunction "4_4") (pintype "passive"))
      (node (ref "X13") (pin "4") (pinfunction "4_4") (pintype "passive"))
      (node (ref "X14") (pin "4") (pinfunction "4_4") (pintype "passive"))
      (node (ref "X15") (pin "4") (pinfunction "4_4") (pintype "passive"))
      (node (ref "X16") (pin "4") (pinfunction "4_4") (pintype "passive"))
      (node (ref "X17") (pin "4") (pinfunction "4_4") (pintype "passive"))
      (node (ref "X18") (pin "4") (pinfunction "4_4") (pintype "passive"))
      (node (ref "X19") (pin "4") (pinfunction "4_4") (pintype "passive"))
      (node (ref "X2") (pin "4") (pinfunction "4_4") (pintype "passive"))
      (node (ref "X20") (pin "4") (pinfunction "4_4") (pintype "passive"))
      (node (ref "X21") (pin "4") (pinfunction "4_4") (pintype "passive"))
      (node (ref "X26") (pin "4") (pinfunction "4_4") (pintype "passive"))
      (node (ref "X3") (pin "4") (pinfunction "4_4") (pintype "passive"))
      (node (ref "X4") (pin "4") (pinfunction "4_4") (pintype "passive"))
      (node (ref "X5") (pin "4") (pinfunction "4_4") (pintype "passive"))
      (node (ref "X6") (pin "4") (pinfunction "4_4") (pintype "passive"))
      (node (ref "X7") (pin "4") (pinfunction "4_4") (pintype "passive"))
      (node (ref "X8") (pin "4") (pinfunction "4_4") (pintype "passive"))
      (node (ref "X9") (pin "4") (pinfunction "4_4") (pintype "passive"))
    )
    (net (code "2") (name "Net-(E1-Pad5)") (class "Default")
      (node (ref "E1") (pin "5") (pinfunction "5_5") (pintype "bidirectional"))
      (node (ref "F1") (pin "2") (pinfunction "2_2") (pintype "passive"))
      (node (ref "J1") (pin "A4B9") (pinfunction "VBUS_A4B9") (pintype "power_in"))
      (node (ref "J1") (pin "B4A9") (pinfunction "VBUS_B4A9") (pintype "power_in"))
    )
    (net (code "3") (name "Net-(E2-Pad5)") (class "Default")
      (node (ref "E2") (pin "5") (pinfunction "5_5") (pintype "bidirectional"))
      (node (ref "F2") (pin "2") (pinfunction "2_2") (pintype "passive"))
      (node (ref "J26") (pin "A4B9") (pinfunction "VBUS_A4B9") (pintype "power_in"))
      (node (ref "J26") (pin "B4A9") (pinfunction "VBUS_B4A9") (pintype "power_in"))
    )
    (net (code "4") (name "Net-(E3-Pad5)") (class "Default")
      (node (ref "E3") (pin "5") (pinfunction "5_5") (pintype "bidirectional"))
      (node (ref "F3") (pin "2") (pinfunction "2_2") (pintype "passive"))
      (node (ref "J2") (pin "A4B9") (pinfunction "VBUS_A4B9") (pintype "power_in"))
      (node (ref "J2") (pin "B4A9") (pinfunction "VBUS_B4A9") (pintype "power_in"))
    )
    (net (code "5") (name "Net-(E4-Pad5)") (class "Default")
      (node (ref "E4") (pin "5") (pinfunction "5_5") (pintype "bidirectional"))
      (node (ref "F4") (pin "2") (pinfunction "2_2") (pintype "passive"))
      (node (ref "J3") (pin "A4B9") (pinfunction "VBUS_A4B9") (pintype "power_in"))
      (node (ref "J3") (pin "B4A9") (pinfunction "VBUS_B4A9") (pintype "power_in"))
    )
    (net (code "6") (name "Net-(E5-Pad5)") (class "Default")
      (node (ref "E5") (pin "5") (pinfunction "5_5") (pintype "bidirectional"))
      (node (ref "F5") (pin "2") (pinfunction "2_2") (pintype "passive"))
      (node (ref "J4") (pin "A4B9") (pinfunction "VBUS_A4B9") (pintype "power_in"))
      (node (ref "J4") (pin "B4A9") (pinfunction "VBUS_B4A9") (pintype "power_in"))
    )
    (net (code "7") (name "Net-(E6-Pad5)") (class "Default")
      (node (ref "E6") (pin "5") (pinfunction "5_5") (pintype "bidirectional"))
      (node (ref "F6") (pin "2") (pinfunction "2_2") (pintype "passive"))
      (node (ref "J5") (pin "A4B9") (pinfunction "VBUS_A4B9") (pintype "power_in"))
      (node (ref "J5") (pin "B4A9") (pinfunction "VBUS_B4A9") (pintype "power_in"))
    )
    (net (code "8") (name "Net-(E7-Pad5)") (class "Default")
      (node (ref "E7") (pin "5") (pinfunction "5_5") (pintype "bidirectional"))
      (node (ref "F7") (pin "2") (pinfunction "2_2") (pintype "passive"))
      (node (ref "J6") (pin "A4B9") (pinfunction "VBUS_A4B9") (pintype "power_in"))
      (node (ref "J6") (pin "B4A9") (pinfunction "VBUS_B4A9") (pintype "power_in"))
    )
    (net (code "9") (name "Net-(E8-Pad5)") (class "Default")
      (node (ref "E8") (pin "5") (pinfunction "5_5") (pintype "bidirectional"))
      (node (ref "F8") (pin "2") (pinfunction "2_2") (pintype "passive"))
      (node (ref "J7") (pin "A4B9") (pinfunction "VBUS_A4B9") (pintype "power_in"))
      (node (ref "J7") (pin "B4A9") (pinfunction "VBUS_B4A9") (pintype "power_in"))
    )
    (net (code "10") (name "Net-(E9-Pad5)") (class "Default")
      (node (ref "E9") (pin "5") (pinfunction "5_5") (pintype "bidirectional"))
      (node (ref "F9") (pin "2") (pinfunction "2_2") (pintype "passive"))
      (node (ref "J8") (pin "A4B9") (pinfunction "VBUS_A4B9") (pintype "power_in"))
      (node (ref "J8") (pin "B4A9") (pinfunction "VBUS_B4A9") (pintype "power_in"))
    )
    (net (code "11") (name "Net-(E10-Pad5)") (class "Default")
      (node (ref "E10") (pin "5") (pinfunction "5_5") (pintype "bidirectional"))
      (node (ref "F10") (pin "2") (pinfunction "2_2") (pintype "passive"))
      (node (ref "J9") (pin "A4B9") (pinfunction "VBUS_A4B9") (pintype "power_in"))
      (node (ref "J9") (pin "B4A9") (pinfunction "VBUS_B4A9") (pintype "power_in"))
    )
    (net (code "12") (name "Net-(E11-Pad5)") (class "Default")
      (node (ref "E11") (pin "5") (pinfunction "5_5") (pintype "bidirectional"))
      (node (ref "F11") (pin "2") (pinfunction "2_2") (pintype "passive"))
      (node (ref "J10") (pin "A4B9") (pinfunction "VBUS_A4B9") (pintype "power_in"))
      (node (ref "J10") (pin "B4A9") (pinfunction "VBUS_B4A9") (pintype "power_in"))
    )
    (net (code "13") (name "Net-(E12-Pad5)") (class "Default")
      (node (ref "E12") (pin "5") (pinfunction "5_5") (pintype "bidirectional"))
      (node (ref "F12") (pin "2") (pinfunction "2_2") (pintype "passive"))
      (node (ref "J11") (pin "A4B9") (pinfunction "VBUS_A4B9") (pintype "power_in"))
      (node (ref "J11") (pin "B4A9") (pinfunction "VBUS_B4A9") (pintype "power_in"))
    )
    (net (code "14") (name "Net-(E13-Pad5)") (class "Default")
      (node (ref "E13") (pin "5") (pinfunction "5_5") (pintype "bidirectional"))
      (node (ref "F13") (pin "2") (pinfunction "2_2") (pintype "passive"))
      (node (ref "J12") (pin "A4B9") (pinfunction "VBUS_A4B9") (pintype "power_in"))
      (node (ref "J12") (pin "B4A9") (pinfunction "VBUS_B4A9") (pintype "power_in"))
    )
    (net (code "15") (name "Net-(E14-Pad5)") (class "Default")
      (node (ref "E14") (pin "5") (pinfunction "5_5") (pintype "bidirectional"))
      (node (ref "F14") (pin "2") (pinfunction "2_2") (pintype "passive"))
      (node (ref "J13") (pin "A4B9") (pinfunction "VBUS_A4B9") (pintype "power_in"))
      (node (ref "J13") (pin "B4A9") (pinfunction "VBUS_B4A9") (pintype "power_in"))
    )
    (net (code "16") (name "Net-(E15-Pad5)") (class "Default")
      (node (ref "E15") (pin "5") (pinfunction "5_5") (pintype "bidirectional"))
      (node (ref "F15") (pin "2") (pinfunction "2_2") (pintype "passive"))
      (node (ref "J14") (pin "A4B9") (pinfunction "VBUS_A4B9") (pintype "power_in"))
      (node (ref "J14") (pin "B4A9") (pinfunction "VBUS_B4A9") (pintype "power_in"))
    )
    (net (code "17") (name "Net-(E16-Pad5)") (class "Default")
      (node (ref "E16") (pin "5") (pinfunction "5_5") (pintype "bidirectional"))
      (node (ref "F16") (pin "2") (pinfunction "2_2") (pintype "passive"))
      (node (ref "J15") (pin "A4B9") (pinfunction "VBUS_A4B9") (pintype "power_in"))
      (node (ref "J15") (pin "B4A9") (pinfunction "VBUS_B4A9") (pintype "power_in"))
    )
    (net (code "18") (name "Net-(E17-Pad5)") (class "Default")
      (node (ref "E17") (pin "5") (pinfunction "5_5") (pintype "bidirectional"))
      (node (ref "F17") (pin "2") (pinfunction "2_2") (pintype "passive"))
      (node (ref "J16") (pin "A4B9") (pinfunction "VBUS_A4B9") (pintype "power_in"))
      (node (ref "J16") (pin "B4A9") (pinfunction "VBUS_B4A9") (pintype "power_in"))
    )
    (net (code "19") (name "Net-(E18-Pad5)") (class "Default")
      (node (ref "E18") (pin "5") (pinfunction "5_5") (pintype "bidirectional"))
      (node (ref "F18") (pin "2") (pinfunction "2_2") (pintype "passive"))
      (node (ref "J17") (pin "A4B9") (pinfunction "VBUS_A4B9") (pintype "power_in"))
      (node (ref "J17") (pin "B4A9") (pinfunction "VBUS_B4A9") (pintype "power_in"))
    )
    (net (code "20") (name "Net-(E19-Pad5)") (class "Default")
      (node (ref "E19") (pin "5") (pinfunction "5_5") (pintype "bidirectional"))
      (node (ref "F19") (pin "2") (pinfunction "2_2") (pintype "passive"))
      (node (ref "J18") (pin "A4B9") (pinfunction "VBUS_A4B9") (pintype "power_in"))
      (node (ref "J18") (pin "B4A9") (pinfunction "VBUS_B4A9") (pintype "power_in"))
    )
    (net (code "21") (name "Net-(E20-Pad5)") (class "Default")
      (node (ref "E20") (pin "5") (pinfunction "5_5") (pintype "bidirectional"))
      (node (ref "F20") (pin "2") (pinfunction "2_2") (pintype "passive"))
      (node (ref "J19") (pin "A4B9") (pinfunction "VBUS_A4B9") (pintype "power_in"))
      (node (ref "J19") (pin "B4A9") (pinfunction "VBUS_B4A9") (pintype "power_in"))
    )
    (net (code "22") (name "Net-(E21-Pad5)") (class "Default")
      (node (ref "E21") (pin "5") (pinfunction "5_5") (pintype "bidirectional"))
      (node (ref "F21") (pin "2") (pinfunction "2_2") (pintype "passive"))
      (node (ref "J20") (pin "A4B9") (pinfunction "VBUS_A4B9") (pintype "power_in"))
      (node (ref "J20") (pin "B4A9") (pinfunction "VBUS_B4A9") (pintype "power_in"))
    )
    (net (code "23") (name "Net-(E22-Pad5)") (class "Default")
      (node (ref "E22") (pin "5") (pinfunction "5_5") (pintype "bidirectional"))
      (node (ref "F22") (pin "2") (pinfunction "2_2") (pintype "passive"))
      (node (ref "J21") (pin "A4B9") (pinfunction "VBUS_A4B9") (pintype "power_in"))
      (node (ref "J21") (pin "B4A9") (pinfunction "VBUS_B4A9") (pintype "power_in"))
    )
    (net (code "24") (name "Net-(F1-Pad1)") (class "Default")
      (node (ref "F1") (pin "1") (pinfunction "1_1") (pintype "passive"))
      (node (ref "X1") (pin "1") (pinfunction "1_1") (pintype "passive"))
    )
    (net (code "25") (name "Net-(F2-Pad1)") (class "Default")
      (node (ref "F2") (pin "1") (pinfunction "1_1") (pintype "passive"))
      (node (ref "X26") (pin "1") (pinfunction "1_1") (pintype "passive"))
    )
    (net (code "26") (name "Net-(F3-Pad1)") (class "Default")
      (node (ref "F3") (pin "1") (pinfunction "1_1") (pintype "passive"))
      (node (ref "X2") (pin "1") (pinfunction "1_1") (pintype "passive"))
    )
    (net (code "27") (name "Net-(F4-Pad1)") (class "Default")
      (node (ref "F4") (pin "1") (pinfunction "1_1") (pintype "passive"))
      (node (ref "X3") (pin "1") (pinfunction "1_1") (pintype "passive"))
    )
    (net (code "28") (name "Net-(F5-Pad1)") (class "Default")
      (node (ref "F5") (pin "1") (pinfunction "1_1") (pintype "passive"))
      (node (ref "X4") (pin "1") (pinfunction "1_1") (pintype "passive"))
    )
    (net (code "29") (name "Net-(F6-Pad1)") (class "Default")
      (node (ref "F6") (pin "1") (pinfunction "1_1") (pintype "passive"))
      (node (ref "X5") (pin "1") (pinfunction "1_1") (pintype "passive"))
    )
    (net (code "30") (name "Net-(F7-Pad1)") (class "Default")
      (node (ref "F7") (pin "1") (pinfunction "1_1") (pintype "passive"))
      (node (ref "X6") (pin "1") (pinfunction "1_1") (pintype "passive"))
    )
    (net (code "31") (name "Net-(F8-Pad1)") (class "Default")
      (node (ref "F8") (pin "1") (pinfunction "1_1") (pintype "passive"))
      (node (ref "X7") (pin "1") (pinfunction "1_1") (pintype "passive"))
    )
    (net (code "32") (name "Net-(F9-Pad1)") (class "Default")
      (node (ref "F9") (pin "1") (pinfunction "1_1") (pintype "passive"))
      (node (ref "X8") (pin "1") (pinfunction "1_1") (pintype "passive"))
    )
    (net (code "33") (name "Net-(F10-Pad1)") (class "Default")
      (node (ref "F10") (pin "1") (pinfunction "1_1") (pintype "passive"))
      (node (ref "X9") (pin "1") (pinfunction "1_1") (pintype "passive"))
    )
    (net (code "34") (name "Net-(F11-Pad1)") (class "Default")
      (node (ref "F11") (pin "1") (pinfunction "1_1") (pintype "passive"))
      (node (ref "X10") (pin "1") (pinfunction "1_1") (pintype "passive"))
    )
    (net (code "35") (name "Net-(F12-Pad1)") (class "Default")
      (node (ref "F12") (pin "1") (pinfunction "1_1") (pintype "passive"))
      (node (ref "X11") (pin "1") (pinfunction "1_1") (pintype "passive"))
    )
    (net (code "36") (name "Net-(F13-Pad1)") (class "Default")
      (node (ref "F13") (pin "1") (pinfunction "1_1") (pintype "passive"))
      (node (ref "X12") (pin "1") (pinfunction "1_1") (pintype "passive"))
    )
    (net (code "37") (name "Net-(F14-Pad1)") (class "Default")
      (node (ref "F14") (pin "1") (pinfunction "1_1") (pintype "passive"))
      (node (ref "X13") (pin "1") (pinfunction "1_1") (pintype "passive"))
    )
    (net (code "38") (name "Net-(F15-Pad1)") (class "Default")
      (node (ref "F15") (pin "1") (pinfunction "1_1") (pintype "passive"))
      (node (ref "X14") (pin "1") (pinfunction "1_1") (pintype "passive"))
    )
    (net (code "39") (name "Net-(F16-Pad1)") (class "Default")
      (node (ref "F16") (pin "1") (pinfunction "1_1") (pintype "passive"))
      (node (ref "X15") (pin "1") (pinfunction "1_1") (pintype "passive"))
    )
    (net (code "40") (name "Net-(F17-Pad1)") (class "Default")
      (node (ref "F17") (pin "1") (pinfunction "1_1") (pintype "passive"))
      (node (ref "X16") (pin "1") (pinfunction "1_1") (pintype "passive"))
    )
    (net (code "41") (name "Net-(F18-Pad1)") (class "Default")
      (node (ref "F18") (pin "1") (pinfunction "1_1") (pintype "passive"))
      (node (ref "X17") (pin "1") (pinfunction "1_1") (pintype "passive"))
    )
    (net (code "42") (name "Net-(F19-Pad1)") (class "Default")
      (node (ref "F19") (pin "1") (pinfunction "1_1") (pintype "passive"))
      (node (ref "X18") (pin "1") (pinfunction "1_1") (pintype "passive"))
    )
    (net (code "43") (name "Net-(F20-Pad1)") (class "Default")
      (node (ref "F20") (pin "1") (pinfunction "1_1") (pintype "passive"))
      (node (ref "X19") (pin "1") (pinfunction "1_1") (pintype "passive"))
    )
    (net (code "44") (name "Net-(F21-Pad1)") (class "Default")
      (node (ref "F21") (pin "1") (pinfunction "1_1") (pintype "passive"))
      (node (ref "X20") (pin "1") (pinfunction "1_1") (pintype "passive"))
    )
    (net (code "45") (name "Net-(F22-Pad1)") (class "Default")
      (node (ref "F22") (pin "1") (pinfunction "1_1") (pintype "passive"))
      (node (ref "X21") (pin "1") (pinfunction "1_1") (pintype "passive"))
    )
    (net (code "46") (name "Net-(J1-CC1)") (class "Default")
      (node (ref "J1") (pin "A5") (pinfunction "CC1_A5") (pintype "bidirectional"))
      (node (ref "R1") (pin "2") (pinfunction "2_2") (pintype "passive"))
    )
    (net (code "47") (name "Net-(J1-CC2)") (class "Default")
      (node (ref "J1") (pin "B5") (pinfunction "CC2_B5") (pintype "bidirectional"))
      (node (ref "R2") (pin "1") (pinfunction "1_1") (pintype "passive"))
    )
    (net (code "48") (name "Net-(J1-DN1)") (class "Default")
      (node (ref "E1") (pin "1") (pinfunction "1_1") (pintype "bidirectional"))
      (node (ref "J1") (pin "A7") (pinfunction "DN1_A7") (pintype "bidirectional"))
      (node (ref "J1") (pin "B7") (pinfunction "DN2_B7") (pintype "bidirectional"))
      (node (ref "X1") (pin "2") (pinfunction "2_2") (pintype "passive"))
    )
    (net (code "49") (name "Net-(J1-DP1)") (class "Default")
      (node (ref "E1") (pin "4") (pinfunction "4_4") (pintype "bidirectional"))
      (node (ref "J1") (pin "A6") (pinfunction "DP1_A6") (pintype "bidirectional"))
      (node (ref "J1") (pin "B6") (pinfunction "DP2_B6") (pintype "bidirectional"))
      (node (ref "X1") (pin "3") (pinfunction "3_3") (pintype "passive"))
    )
    (net (code "50") (name "Net-(J2-CC1)") (class "Default")
      (node (ref "J2") (pin "A5") (pinfunction "CC1_A5") (pintype "bidirectional"))
      (node (ref "R5") (pin "2") (pinfunction "2_2") (pintype "passive"))
    )
    (net (code "51") (name "Net-(J2-CC2)") (class "Default")
      (node (ref "J2") (pin "B5") (pinfunction "CC2_B5") (pintype "bidirectional"))
      (node (ref "R6") (pin "1") (pinfunction "1_1") (pintype "passive"))
    )
    (net (code "52") (name "Net-(J2-DN1)") (class "Default")
      (node (ref "E3") (pin "1") (pinfunction "1_1") (pintype "bidirectional"))
      (node (ref "J2") (pin "A7") (pinfunction "DN1_A7") (pintype "bidirectional"))
      (node (ref "J2") (pin "B7") (pinfunction "DN2_B7") (pintype "bidirectional"))
      (node (ref "X2") (pin "2") (pinfunction "2_2") (pintype "passive"))
    )
    (net (code "53") (name "Net-(J2-DP1)") (class "Default")
      (node (ref "E3") (pin "4") (pinfunction "4_4") (pintype "bidirectional"))
      (node (ref "J2") (pin "A6") (pinfunction "DP1_A6") (pintype "bidirectional"))
      (node (ref "J2") (pin "B6") (pinfunction "DP2_B6") (pintype "bidirectional"))
      (node (ref "X2") (pin "3") (pinfunction "3_3") (pintype "passive"))
    )
    (net (code "54") (name "Net-(J3-CC1)") (class "Default")
      (node (ref "J3") (pin "A5") (pinfunction "CC1_A5") (pintype "bidirectional"))
      (node (ref "R7") (pin "2") (pinfunction "2_2") (pintype "passive"))
    )
    (net (code "55") (name "Net-(J3-CC2)") (class "Default")
      (node (ref "J3") (pin "B5") (pinfunction "CC2_B5") (pintype "bidirectional"))
      (node (ref "R8") (pin "1") (pinfunction "1_1") (pintype "passive"))
    )
    (net (code "56") (name "Net-(J3-DN1)") (class "Default")
      (node (ref "E4") (pin "1") (pinfunction "1_1") (pintype "bidirectional"))
      (node (ref "J3") (pin "A7") (pinfunction "DN1_A7") (pintype "bidirectional"))
      (node (ref "J3") (pin "B7") (pinfunction "DN2_B7") (pintype "bidirectional"))
      (node (ref "X3") (pin "2") (pinfunction "2_2") (pintype "passive"))
    )
    (net (code "57") (name "Net-(J3-DP1)") (class "Default")
      (node (ref "E4") (pin "4") (pinfunction "4_4") (pintype "bidirectional"))
      (node (ref "J3") (pin "A6") (pinfunction "DP1_A6") (pintype "bidirectional"))
      (node (ref "J3") (pin "B6") (pinfunction "DP2_B6") (pintype "bidirectional"))
      (node (ref "X3") (pin "3") (pinfunction "3_3") (pintype "passive"))
    )
    (net (code "58") (name "Net-(J4-CC1)") (class "Default")
      (node (ref "J4") (pin "A5") (pinfunction "CC1_A5") (pintype "bidirectional"))
      (node (ref "R9") (pin "2") (pinfunction "2_2") (pintype "passive"))
    )
    (net (code "59") (name "Net-(J4-CC2)") (class "Default")
      (node (ref "J4") (pin "B5") (pinfunction "CC2_B5") (pintype "bidirectional"))
      (node (ref "R10") (pin "1") (pinfunction "1_1") (pintype "passive"))
    )
    (net (code "60") (name "Net-(J4-DN1)") (class "Default")
      (node (ref "E5") (pin "1") (pinfunction "1_1") (pintype "bidirectional"))
      (node (ref "J4") (pin "A7") (pinfunction "DN1_A7") (pintype "bidirectional"))
      (node (ref "J4") (pin "B7") (pinfunction "DN2_B7") (pintype "bidirectional"))
      (node (ref "X4") (pin "2") (pinfunction "2_2") (pintype "passive"))
    )
    (net (code "61") (name "Net-(J4-DP1)") (class "Default")
      (node (ref "E5") (pin "4") (pinfunction "4_4") (pintype "bidirectional"))
      (node (ref "J4") (pin "A6") (pinfunction "DP1_A6") (pintype "bidirectional"))
      (node (ref "J4") (pin "B6") (pinfunction "DP2_B6") (pintype "bidirectional"))
      (node (ref "X4") (pin "3") (pinfunction "3_3") (pintype "passive"))
    )
    (net (code "62") (name "Net-(J5-CC1)") (class "Default")
      (node (ref "J5") (pin "A5") (pinfunction "CC1_A5") (pintype "bidirectional"))
      (node (ref "R11") (pin "2") (pinfunction "2_2") (pintype "passive"))
    )
    (net (code "63") (name "Net-(J5-CC2)") (class "Default")
      (node (ref "J5") (pin "B5") (pinfunction "CC2_B5") (pintype "bidirectional"))
      (node (ref "R12") (pin "1") (pinfunction "1_1") (pintype "passive"))
    )
    (net (code "64") (name "Net-(J5-DN1)") (class "Default")
      (node (ref "E6") (pin "1") (pinfunction "1_1") (pintype "bidirectional"))
      (node (ref "J5") (pin "A7") (pinfunction "DN1_A7") (pintype "bidirectional"))
      (node (ref "J5") (pin "B7") (pinfunction "DN2_B7") (pintype "bidirectional"))
      (node (ref "X5") (pin "2") (pinfunction "2_2") (pintype "passive"))
    )
    (net (code "65") (name "Net-(J5-DP1)") (class "Default")
      (node (ref "E6") (pin "4") (pinfunction "4_4") (pintype "bidirectional"))
      (node (ref "J5") (pin "A6") (pinfunction "DP1_A6") (pintype "bidirectional"))
      (node (ref "J5") (pin "B6") (pinfunction "DP2_B6") (pintype "bidirectional"))
      (node (ref "X5") (pin "3") (pinfunction "3_3") (pintype "passive"))
    )
    (net (code "66") (name "Net-(J6-CC1)") (class "Default")
      (node (ref "J6") (pin "A5") (pinfunction "CC1_A5") (pintype "bidirectional"))
      (node (ref "R13") (pin "2") (pinfunction "2_2") (pintype "passive"))
    )
    (net (code "67") (name "Net-(J6-CC2)") (class "Default")
      (node (ref "J6") (pin "B5") (pinfunction "CC2_B5") (pintype "bidirectional"))
      (node (ref "R14") (pin "1") (pinfunction "1_1") (pintype "passive"))
    )
    (net (code "68") (name "Net-(J6-DN1)") (class "Default")
      (node (ref "E7") (pin "1") (pinfunction "1_1") (pintype "bidirectional"))
      (node (ref "J6") (pin "A7") (pinfunction "DN1_A7") (pintype "bidirectional"))
      (node (ref "J6") (pin "B7") (pinfunction "DN2_B7") (pintype "bidirectional"))
      (node (ref "X6") (pin "2") (pinfunction "2_2") (pintype "passive"))
    )
    (net (code "69") (name "Net-(J6-DP1)") (class "Default")
      (node (ref "E7") (pin "4") (pinfunction "4_4") (pintype "bidirectional"))
      (node (ref "J6") (pin "A6") (pinfunction "DP1_A6") (pintype "bidirectional"))
      (node (ref "J6") (pin "B6") (pinfunction "DP2_B6") (pintype "bidirectional"))
      (node (ref "X6") (pin "3") (pinfunction "3_3") (pintype "passive"))
    )
    (net (code "70") (name "Net-(J7-CC1)") (class "Default")
      (node (ref "J7") (pin "A5") (pinfunction "CC1_A5") (pintype "bidirectional"))
      (node (ref "R15") (pin "2") (pinfunction "2_2") (pintype "passive"))
    )
    (net (code "71") (name "Net-(J7-CC2)") (class "Default")
      (node (ref "J7") (pin "B5") (pinfunction "CC2_B5") (pintype "bidirectional"))
      (node (ref "R16") (pin "1") (pinfunction "1_1") (pintype "passive"))
    )
    (net (code "72") (name "Net-(J7-DN1)") (class "Default")
      (node (ref "E8") (pin "1") (pinfunction "1_1") (pintype "bidirectional"))
      (node (ref "J7") (pin "A7") (pinfunction "DN1_A7") (pintype "bidirectional"))
      (node (ref "J7") (pin "B7") (pinfunction "DN2_B7") (pintype "bidirectional"))
      (node (ref "X7") (pin "2") (pinfunction "2_2") (pintype "passive"))
    )
    (net (code "73") (name "Net-(J7-DP1)") (class "Default")
      (node (ref "E8") (pin "4") (pinfunction "4_4") (pintype "bidirectional"))
      (node (ref "J7") (pin "A6") (pinfunction "DP1_A6") (pintype "bidirectional"))
      (node (ref "J7") (pin "B6") (pinfunction "DP2_B6") (pintype "bidirectional"))
      (node (ref "X7") (pin "3") (pinfunction "3_3") (pintype "passive"))
    )
    (net (code "74") (name "Net-(J8-CC1)") (class "Default")
      (node (ref "J8") (pin "A5") (pinfunction "CC1_A5") (pintype "bidirectional"))
      (node (ref "R17") (pin "2") (pinfunction "2_2") (pintype "passive"))
    )
    (net (code "75") (name "Net-(J8-CC2)") (class "Default")
      (node (ref "J8") (pin "B5") (pinfunction "CC2_B5") (pintype "bidirectional"))
      (node (ref "R18") (pin "1") (pinfunction "1_1") (pintype "passive"))
    )
    (net (code "76") (name "Net-(J8-DN1)") (class "Default")
      (node (ref "E9") (pin "1") (pinfunction "1_1") (pintype "bidirectional"))
      (node (ref "J8") (pin "A7") (pinfunction "DN1_A7") (pintype "bidirectional"))
      (node (ref "J8") (pin "B7") (pinfunction "DN2_B7") (pintype "bidirectional"))
      (node (ref "X8") (pin "2") (pinfunction "2_2") (pintype "passive"))
    )
    (net (code "77") (name "Net-(J8-DP1)") (class "Default")
      (node (ref "E9") (pin "4") (pinfunction "4_4") (pintype "bidirectional"))
      (node (ref "J8") (pin "A6") (pinfunction "DP1_A6") (pintype "bidirectional"))
      (node (ref "J8") (pin "B6") (pinfunction "DP2_B6") (pintype "bidirectional"))
      (node (ref "X8") (pin "3") (pinfunction "3_3") (pintype "passive"))
    )
    (net (code "78") (name "Net-(J9-CC1)") (class "Default")
      (node (ref "J9") (pin "A5") (pinfunction "CC1_A5") (pintype "bidirectional"))
      (node (ref "R19") (pin "2") (pinfunction "2_2") (pintype "passive"))
    )
    (net (code "79") (name "Net-(J9-CC2)") (class "Default")
      (node (ref "J9") (pin "B5") (pinfunction "CC2_B5") (pintype "bidirectional"))
      (node (ref "R20") (pin "1") (pinfunction "1_1") (pintype "passive"))
    )
    (net (code "80") (name "Net-(J9-DN1)") (class "Default")
      (node (ref "E10") (pin "1") (pinfunction "1_1") (pintype "bidirectional"))
      (node (ref "J9") (pin "A7") (pinfunction "DN1_A7") (pintype "bidirectional"))
      (node (ref "J9") (pin "B7") (pinfunction "DN2_B7") (pintype "bidirectional"))
      (node (ref "X9") (pin "2") (pinfunction "2_2") (pintype "passive"))
    )
    (net (code "81") (name "Net-(J9-DP1)") (class "Default")
      (node (ref "E10") (pin "4") (pinfunction "4_4") (pintype "bidirectional"))
      (node (ref "J9") (pin "A6") (pinfunction "DP1_A6") (pintype "bidirectional"))
      (node (ref "J9") (pin "B6") (pinfunction "DP2_B6") (pintype "bidirectional"))
      (node (ref "X9") (pin "3") (pinfunction "3_3") (pintype "passive"))
    )
    (net (code "82") (name "Net-(J10-CC1)") (class "Default")
      (node (ref "J10") (pin "A5") (pinfunction "CC1_A5") (pintype "bidirectional"))
      (node (ref "R21") (pin "2") (pinfunction "2_2") (pintype "passive"))
    )
    (net (code "83") (name "Net-(J10-CC2)") (class "Default")
      (node (ref "J10") (pin "B5") (pinfunction "CC2_B5") (pintype "bidirectional"))
      (node (ref "R22") (pin "1") (pinfunction "1_1") (pintype "passive"))
    )
    (net (code "84") (name "Net-(J10-DN1)") (class "Default")
      (node (ref "E11") (pin "1") (pinfunction "1_1") (pintype "bidirectional"))
      (node (ref "J10") (pin "A7") (pinfunction "DN1_A7") (pintype "bidirectional"))
      (node (ref "J10") (pin "B7") (pinfunction "DN2_B7") (pintype "bidirectional"))
      (node (ref "X10") (pin "2") (pinfunction "2_2") (pintype "passive"))
    )
    (net (code "85") (name "Net-(J10-DP1)") (class "Default")
      (node (ref "E11") (pin "4") (pinfunction "4_4") (pintype "bidirectional"))
      (node (ref "J10") (pin "A6") (pinfunction "DP1_A6") (pintype "bidirectional"))
      (node (ref "J10") (pin "B6") (pinfunction "DP2_B6") (pintype "bidirectional"))
      (node (ref "X10") (pin "3") (pinfunction "3_3") (pintype "passive"))
    )
    (net (code "86") (name "Net-(J11-CC1)") (class "Default")
      (node (ref "J11") (pin "A5") (pinfunction "CC1_A5") (pintype "bidirectional"))
      (node (ref "R23") (pin "2") (pinfunction "2_2") (pintype "passive"))
    )
    (net (code "87") (name "Net-(J11-CC2)") (class "Default")
      (node (ref "J11") (pin "B5") (pinfunction "CC2_B5") (pintype "bidirectional"))
      (node (ref "R24") (pin "1") (pinfunction "1_1") (pintype "passive"))
    )
    (net (code "88") (name "Net-(J11-DN1)") (class "Default")
      (node (ref "E12") (pin "1") (pinfunction "1_1") (pintype "bidirectional"))
      (node (ref "J11") (pin "A7") (pinfunction "DN1_A7") (pintype "bidirectional"))
      (node (ref "J11") (pin "B7") (pinfunction "DN2_B7") (pintype "bidirectional"))
      (node (ref "X11") (pin "2") (pinfunction "2_2") (pintype "passive"))
    )
    (net (code "89") (name "Net-(J11-DP1)") (class "Default")
      (node (ref "E12") (pin "4") (pinfunction "4_4") (pintype "bidirectional"))
      (node (ref "J11") (pin "A6") (pinfunction "DP1_A6") (pintype "bidirectional"))
      (node (ref "J11") (pin "B6") (pinfunction "DP2_B6") (pintype "bidirectional"))
      (node (ref "X11") (pin "3") (pinfunction "3_3") (pintype "passive"))
    )
    (net (code "90") (name "Net-(J12-CC1)") (class "Default")
      (node (ref "J12") (pin "A5") (pinfunction "CC1_A5") (pintype "bidirectional"))
      (node (ref "R25") (pin "2") (pinfunction "2_2") (pintype "passive"))
    )
    (net (code "91") (name "Net-(J12-CC2)") (class "Default")
      (node (ref "J12") (pin "B5") (pinfunction "CC2_B5") (pintype "bidirectional"))
      (node (ref "R26") (pin "1") (pinfunction "1_1") (pintype "passive"))
    )
    (net (code "92") (name "Net-(J12-DN1)") (class "Default")
      (node (ref "E13") (pin "1") (pinfunction "1_1") (pintype "bidirectional"))
      (node (ref "J12") (pin "A7") (pinfunction "DN1_A7") (pintype "bidirectional"))
      (node (ref "J12") (pin "B7") (pinfunction "DN2_B7") (pintype "bidirectional"))
      (node (ref "X12") (pin "2") (pinfunction "2_2") (pintype "passive"))
    )
    (net (code "93") (name "Net-(J12-DP1)") (class "Default")
      (node (ref "E13") (pin "4") (pinfunction "4_4") (pintype "bidirectional"))
      (node (ref "J12") (pin "A6") (pinfunction "DP1_A6") (pintype "bidirectional"))
      (node (ref "J12") (pin "B6") (pinfunction "DP2_B6") (pintype "bidirectional"))
      (node (ref "X12") (pin "3") (pinfunction "3_3") (pintype "passive"))
    )
    (net (code "94") (name "Net-(J13-CC1)") (class "Default")
      (node (ref "J13") (pin "A5") (pinfunction "CC1_A5") (pintype "bidirectional"))
      (node (ref "R27") (pin "2") (pinfunction "2_2") (pintype "passive"))
    )
    (net (code "95") (name "Net-(J13-CC2)") (class "Default")
      (node (ref "J13") (pin "B5") (pinfunction "CC2_B5") (pintype "bidirectional"))
      (node (ref "R28") (pin "1") (pinfunction "1_1") (pintype "passive"))
    )
    (net (code "96") (name "Net-(J13-DN1)") (class "Default")
      (node (ref "E14") (pin "1") (pinfunction "1_1") (pintype "bidirectional"))
      (node (ref "J13") (pin "A7") (pinfunction "DN1_A7") (pintype "bidirectional"))
      (node (ref "J13") (pin "B7") (pinfunction "DN2_B7") (pintype "bidirectional"))
      (node (ref "X13") (pin "2") (pinfunction "2_2") (pintype "passive"))
    )
    (net (code "97") (name "Net-(J13-DP1)") (class "Default")
      (node (ref "E14") (pin "4") (pinfunction "4_4") (pintype "bidirectional"))
      (node (ref "J13") (pin "A6") (pinfunction "DP1_A6") (pintype "bidirectional"))
      (node (ref "J13") (pin "B6") (pinfunction "DP2_B6") (pintype "bidirectional"))
      (node (ref "X13") (pin "3") (pinfunction "3_3") (pintype "passive"))
    )
    (net (code "98") (name "Net-(J14-CC1)") (class "Default")
      (node (ref "J14") (pin "A5") (pinfunction "CC1_A5") (pintype "bidirectional"))
      (node (ref "R29") (pin "2") (pinfunction "2_2") (pintype "passive"))
    )
    (net (code "99") (name "Net-(J14-CC2)") (class "Default")
      (node (ref "J14") (pin "B5") (pinfunction "CC2_B5") (pintype "bidirectional"))
      (node (ref "R30") (pin "1") (pinfunction "1_1") (pintype "passive"))
    )
    (net (code "100") (name "Net-(J14-DN1)") (class "Default")
      (node (ref "E15") (pin "1") (pinfunction "1_1") (pintype "bidirectional"))
      (node (ref "J14") (pin "A7") (pinfunction "DN1_A7") (pintype "bidirectional"))
      (node (ref "J14") (pin "B7") (pinfunction "DN2_B7") (pintype "bidirectional"))
      (node (ref "X14") (pin "2") (pinfunction "2_2") (pintype "passive"))
    )
    (net (code "101") (name "Net-(J14-DP1)") (class "Default")
      (node (ref "E15") (pin "4") (pinfunction "4_4") (pintype "bidirectional"))
      (node (ref "J14") (pin "A6") (pinfunction "DP1_A6") (pintype "bidirectional"))
      (node (ref "J14") (pin "B6") (pinfunction "DP2_B6") (pintype "bidirectional"))
      (node (ref "X14") (pin "3") (pinfunction "3_3") (pintype "passive"))
    )
    (net (code "102") (name "Net-(J15-CC1)") (class "Default")
      (node (ref "J15") (pin "A5") (pinfunction "CC1_A5") (pintype "bidirectional"))
      (node (ref "R31") (pin "2") (pinfunction "2_2") (pintype "passive"))
    )
    (net (code "103") (name "Net-(J15-CC2)") (class "Default")
      (node (ref "J15") (pin "B5") (pinfunction "CC2_B5") (pintype "bidirectional"))
      (node (ref "R32") (pin "1") (pinfunction "1_1") (pintype "passive"))
    )
    (net (code "104") (name "Net-(J15-DN1)") (class "Default")
      (node (ref "E16") (pin "1") (pinfunction "1_1") (pintype "bidirectional"))
      (node (ref "J15") (pin "A7") (pinfunction "DN1_A7") (pintype "bidirectional"))
      (node (ref "J15") (pin "B7") (pinfunction "DN2_B7") (pintype "bidirectional"))
      (node (ref "X15") (pin "2") (pinfunction "2_2") (pintype "passive"))
    )
    (net (code "105") (name "Net-(J15-DP1)") (class "Default")
      (node (ref "E16") (pin "4") (pinfunction "4_4") (pintype "bidirectional"))
      (node (ref "J15") (pin "A6") (pinfunction "DP1_A6") (pintype "bidirectional"))
      (node (ref "J15") (pin "B6") (pinfunction "DP2_B6") (pintype "bidirectional"))
      (node (ref "X15") (pin "3") (pinfunction "3_3") (pintype "passive"))
    )
    (net (code "106") (name "Net-(J16-CC1)") (class "Default")
      (node (ref "J16") (pin "A5") (pinfunction "CC1_A5") (pintype "bidirectional"))
      (node (ref "R33") (pin "2") (pinfunction "2_2") (pintype "passive"))
    )
    (net (code "107") (name "Net-(J16-CC2)") (class "Default")
      (node (ref "J16") (pin "B5") (pinfunction "CC2_B5") (pintype "bidirectional"))
      (node (ref "R34") (pin "1") (pinfunction "1_1") (pintype "passive"))
    )
    (net (code "108") (name "Net-(J16-DN1)") (class "Default")
      (node (ref "E17") (pin "1") (pinfunction "1_1") (pintype "bidirectional"))
      (node (ref "J16") (pin "A7") (pinfunction "DN1_A7") (pintype "bidirectional"))
      (node (ref "J16") (pin "B7") (pinfunction "DN2_B7") (pintype "bidirectional"))
      (node (ref "X16") (pin "2") (pinfunction "2_2") (pintype "passive"))
    )
    (net (code "109") (name "Net-(J16-DP1)") (class "Default")
      (node (ref "E17") (pin "4") (pinfunction "4_4") (pintype "bidirectional"))
      (node (ref "J16") (pin "A6") (pinfunction "DP1_A6") (pintype "bidirectional"))
      (node (ref "J16") (pin "B6") (pinfunction "DP2_B6") (pintype "bidirectional"))
      (node (ref "X16") (pin "3") (pinfunction "3_3") (pintype "passive"))
    )
    (net (code "110") (name "Net-(J17-CC1)") (class "Default")
      (node (ref "J17") (pin "A5") (pinfunction "CC1_A5") (pintype "bidirectional"))
      (node (ref "R35") (pin "2") (pinfunction "2_2") (pintype "passive"))
    )
    (net (code "111") (name "Net-(J17-CC2)") (class "Default")
      (node (ref "J17") (pin "B5") (pinfunction "CC2_B5") (pintype "bidirectional"))
      (node (ref "R36") (pin "1") (pinfunction "1_1") (pintype "passive"))
    )
    (net (code "112") (name "Net-(J17-DN1)") (class "Default")
      (node (ref "E18") (pin "1") (pinfunction "1_1") (pintype "bidirectional"))
      (node (ref "J17") (pin "A7") (pinfunction "DN1_A7") (pintype "bidirectional"))
      (node (ref "J17") (pin "B7") (pinfunction "DN2_B7") (pintype "bidirectional"))
      (node (ref "X17") (pin "2") (pinfunction "2_2") (pintype "passive"))
    )
    (net (code "113") (name "Net-(J17-DP1)") (class "Default")
      (node (ref "E18") (pin "4") (pinfunction "4_4") (pintype "bidirectional"))
      (node (ref "J17") (pin "A6") (pinfunction "DP1_A6") (pintype "bidirectional"))
      (node (ref "J17") (pin "B6") (pinfunction "DP2_B6") (pintype "bidirectional"))
      (node (ref "X17") (pin "3") (pinfunction "3_3") (pintype "passive"))
    )
    (net (code "114") (name "Net-(J18-CC1)") (class "Default")
      (node (ref "J18") (pin "A5") (pinfunction "CC1_A5") (pintype "bidirectional"))
      (node (ref "R37") (pin "2") (pinfunction "2_2") (pintype "passive"))
    )
    (net (code "115") (name "Net-(J18-CC2)") (class "Default")
      (node (ref "J18") (pin "B5") (pinfunction "CC2_B5") (pintype "bidirectional"))
      (node (ref "R38") (pin "1") (pinfunction "1_1") (pintype "passive"))
    )
    (net (code "116") (name "Net-(J18-DN1)") (class "Default")
      (node (ref "E19") (pin "1") (pinfunction "1_1") (pintype "bidirectional"))
      (node (ref "J18") (pin "A7") (pinfunction "DN1_A7") (pintype "bidirectional"))
      (node (ref "J18") (pin "B7") (pinfunction "DN2_B7") (pintype "bidirectional"))
      (node (ref "X18") (pin "2") (pinfunction "2_2") (pintype "passive"))
    )
    (net (code "117") (name "Net-(J18-DP1)") (class "Default")
      (node (ref "E19") (pin "4") (pinfunction "4_4") (pintype "bidirectional"))
      (node (ref "J18") (pin "A6") (pinfunction "DP1_A6") (pintype "bidirectional"))
      (node (ref "J18") (pin "B6") (pinfunction "DP2_B6") (pintype "bidirectional"))
      (node (ref "X18") (pin "3") (pinfunction "3_3") (pintype "passive"))
    )
    (net (code "118") (name "Net-(J19-CC1)") (class "Default")
      (node (ref "J19") (pin "A5") (pinfunction "CC1_A5") (pintype "bidirectional"))
      (node (ref "R39") (pin "2") (pinfunction "2_2") (pintype "passive"))
    )
    (net (code "119") (name "Net-(J19-CC2)") (class "Default")
      (node (ref "J19") (pin "B5") (pinfunction "CC2_B5") (pintype "bidirectional"))
      (node (ref "R40") (pin "1") (pinfunction "1_1") (pintype "passive"))
    )
    (net (code "120") (name "Net-(J19-DN1)") (class "Default")
      (node (ref "E20") (pin "1") (pinfunction "1_1") (pintype "bidirectional"))
      (node (ref "J19") (pin "A7") (pinfunction "DN1_A7") (pintype "bidirectional"))
      (node (ref "J19") (pin "B7") (pinfunction "DN2_B7") (pintype "bidirectional"))
      (node (ref "X19") (pin "2") (pinfunction "2_2") (pintype "passive"))
    )
    (net (code "121") (name "Net-(J19-DP1)") (class "Default")
      (node (ref "E20") (pin "4") (pinfunction "4_4") (pintype "bidirectional"))
      (node (ref "J19") (pin "A6") (pinfunction "DP1_A6") (pintype "bidirectional"))
      (node (ref "J19") (pin "B6") (pinfunction "DP2_B6") (pintype "bidirectional"))
      (node (ref "X19") (pin "3") (pinfunction "3_3") (pintype "passive"))
    )
    (net (code "122") (name "Net-(J20-CC1)") (class "Default")
      (node (ref "J20") (pin "A5") (pinfunction "CC1_A5") (pintype "bidirectional"))
      (node (ref "R41") (pin "2") (pinfunction "2_2") (pintype "passive"))
    )
    (net (code "123") (name "Net-(J20-CC2)") (class "Default")
      (node (ref "J20") (pin "B5") (pinfunction "CC2_B5") (pintype "bidirectional"))
      (node (ref "R42") (pin "1") (pinfunction "1_1") (pintype "passive"))
    )
    (net (code "124") (name "Net-(J20-DN1)") (class "Default")
      (node (ref "E21") (pin "1") (pinfunction "1_1") (pintype "bidirectional"))
      (node (ref "J20") (pin "A7") (pinfunction "DN1_A7") (pintype "bidirectional"))
      (node (ref "J20") (pin "B7") (pinfunction "DN2_B7") (pintype "bidirectional"))
      (node (ref "X20") (pin "2") (pinfunction "2_2") (pintype "passive"))
    )
    (net (code "125") (name "Net-(J20-DP1)") (class "Default")
      (node (ref "E21") (pin "4") (pinfunction "4_4") (pintype "bidirectional"))
      (node (ref "J20") (pin "A6") (pinfunction "DP1_A6") (pintype "bidirectional"))
      (node (ref "J20") (pin "B6") (pinfunction "DP2_B6") (pintype "bidirectional"))
      (node (ref "X20") (pin "3") (pinfunction "3_3") (pintype "passive"))
    )
    (net (code "126") (name "Net-(J21-CC1)") (class "Default")
      (node (ref "J21") (pin "A5") (pinfunction "CC1_A5") (pintype "bidirectional"))
      (node (ref "R43") (pin "2") (pinfunction "2_2") (pintype "passive"))
    )
    (net (code "127") (name "Net-(J21-CC2)") (class "Default")
      (node (ref "J21") (pin "B5") (pinfunction "CC2_B5") (pintype "bidirectional"))
      (node (ref "R44") (pin "1") (pinfunction "1_1") (pintype "passive"))
    )
    (net (code "128") (name "Net-(J21-DN1)") (class "Default")
      (node (ref "E22") (pin "1") (pinfunction "1_1") (pintype "bidirectional"))
      (node (ref "J21") (pin "A7") (pinfunction "DN1_A7") (pintype "bidirectional"))
      (node (ref "J21") (pin "B7") (pinfunction "DN2_B7") (pintype "bidirectional"))
      (node (ref "X21") (pin "2") (pinfunction "2_2") (pintype "passive"))
    )
    (net (code "129") (name "Net-(J21-DP1)") (class "Default")
      (node (ref "E22") (pin "4") (pinfunction "4_4") (pintype "bidirectional"))
      (node (ref "J21") (pin "A6") (pinfunction "DP1_A6") (pintype "bidirectional"))
      (node (ref "J21") (pin "B6") (pinfunction "DP2_B6") (pintype "bidirectional"))
      (node (ref "X21") (pin "3") (pinfunction "3_3") (pintype "passive"))
    )
    (net (code "130") (name "Net-(J26-CC1)") (class "Default")
      (node (ref "J26") (pin "A5") (pinfunction "CC1_A5") (pintype "bidirectional"))
      (node (ref "R3") (pin "2") (pinfunction "2_2") (pintype "passive"))
    )
    (net (code "131") (name "Net-(J26-CC2)") (class "Default")
      (node (ref "J26") (pin "B5") (pinfunction "CC2_B5") (pintype "bidirectional"))
      (node (ref "R4") (pin "1") (pinfunction "1_1") (pintype "passive"))
    )
    (net (code "132") (name "Net-(J26-DN1)") (class "Default")
      (node (ref "E2") (pin "1") (pinfunction "1_1") (pintype "bidirectional"))
      (node (ref "J26") (pin "A7") (pinfunction "DN1_A7") (pintype "bidirectional"))
      (node (ref "J26") (pin "B7") (pinfunction "DN2_B7") (pintype "bidirectional"))
      (node (ref "X26") (pin "2") (pinfunction "2_2") (pintype "passive"))
    )
    (net (code "133") (name "Net-(J26-DP1)") (class "Default")
      (node (ref "E2") (pin "4") (pinfunction "4_4") (pintype "bidirectional"))
      (node (ref "J26") (pin "A6") (pinfunction "DP1_A6") (pintype "bidirectional"))
      (node (ref "J26") (pin "B6") (pinfunction "DP2_B6") (pintype "bidirectional"))
      (node (ref "X26") (pin "3") (pinfunction "3_3") (pintype "passive"))
    )
    (net (code "134") (name "unconnected-(E1-Pad3)") (class "Default")
      (node (ref "E1") (pin "3") (pinfunction "3_3") (pintype "bidirectional"))
    )
    (net (code "135") (name "unconnected-(E1-Pad6)") (class "Default")
      (node (ref "E1") (pin "6") (pinfunction "6_6") (pintype "bidirectional"))
    )
    (net (code "136") (name "unconnected-(E2-Pad3)") (class "Default")
      (node (ref "E2") (pin "3") (pinfunction "3_3") (pintype "bidirectional"))
    )
    (net (code "137") (name "unconnected-(E2-Pad6)") (class "Default")
      (node (ref "E2") (pin "6") (pinfunction "6_6") (pintype "bidirectional"))
    )
    (net (code "138") (name "unconnected-(E3-Pad3)") (class "Default")
      (node (ref "E3") (pin "3") (pinfunction "3_3") (pintype "bidirectional"))
    )
    (net (code "139") (name "unconnected-(E3-Pad6)") (class "Default")
      (node (ref "E3") (pin "6") (pinfunction "6_6") (pintype "bidirectional"))
    )
    (net (code "140") (name "unconnected-(E4-Pad3)") (class "Default")
      (node (ref "E4") (pin "3") (pinfunction "3_3") (pintype "bidirectional"))
    )
    (net (code "141") (name "unconnected-(E4-Pad6)") (class "Default")
      (node (ref "E4") (pin "6") (pinfunction "6_6") (pintype "bidirectional"))
    )
    (net (code "142") (name "unconnected-(E5-Pad3)") (class "Default")
      (node (ref "E5") (pin "3") (pinfunction "3_3") (pintype "bidirectional"))
    )
    (net (code "143") (name "unconnected-(E5-Pad6)") (class "Default")
      (node (ref "E5") (pin "6") (pinfunction "6_6") (pintype "bidirectional"))
    )
    (net (code "144") (name "unconnected-(E6-Pad3)") (class "Default")
      (node (ref "E6") (pin "3") (pinfunction "3_3") (pintype "bidirectional"))
    )
    (net (code "145") (name "unconnected-(E6-Pad6)") (class "Default")
      (node (ref "E6") (pin "6") (pinfunction "6_6") (pintype "bidirectional"))
    )
    (net (code "146") (name "unconnected-(E7-Pad3)") (class "Default")
      (node (ref "E7") (pin "3") (pinfunction "3_3") (pintype "bidirectional"))
    )
    (net (code "147") (name "unconnected-(E7-Pad6)") (class "Default")
      (node (ref "E7") (pin "6") (pinfunction "6_6") (pintype "bidirectional"))
    )
    (net (code "148") (name "unconnected-(E8-Pad3)") (class "Default")
      (node (ref "E8") (pin "3") (pinfunction "3_3") (pintype "bidirectional"))
    )
    (net (code "149") (name "unconnected-(E8-Pad6)") (class "Default")
      (node (ref "E8") (pin "6") (pinfunction "6_6") (pintype "bidirectional"))
    )
    (net (code "150") (name "unconnected-(E9-Pad3)") (class "Default")
      (node (ref "E9") (pin "3") (pinfunction "3_3") (pintype "bidirectional"))
    )
    (net (code "151") (name "unconnected-(E9-Pad6)") (class "Default")
      (node (ref "E9") (pin "6") (pinfunction "6_6") (pintype "bidirectional"))
    )
    (net (code "152") (name "unconnected-(E10-Pad3)") (class "Default")
      (node (ref "E10") (pin "3") (pinfunction "3_3") (pintype "bidirectional"))
    )
    (net (code "153") (name "unconnected-(E10-Pad6)") (class "Default")
      (node (ref "E10") (pin "6") (pinfunction "6_6") (pintype "bidirectional"))
    )
    (net (code "154") (name "unconnected-(E11-Pad3)") (class "Default")
      (node (ref "E11") (pin "3") (pinfunction "3_3") (pintype "bidirectional"))
    )
    (net (code "155") (name "unconnected-(E11-Pad6)") (class "Default")
      (node (ref "E11") (pin "6") (pinfunction "6_6") (pintype "bidirectional"))
    )
    (net (code "156") (name "unconnected-(E12-Pad3)") (class "Default")
      (node (ref "E12") (pin "3") (pinfunction "3_3") (pintype "bidirectional"))
    )
    (net (code "157") (name "unconnected-(E12-Pad6)") (class "Default")
      (node (ref "E12") (pin "6") (pinfunction "6_6") (pintype "bidirectional"))
    )
    (net (code "158") (name "unconnected-(E13-Pad3)") (class "Default")
      (node (ref "E13") (pin "3") (pinfunction "3_3") (pintype "bidirectional"))
    )
    (net (code "159") (name "unconnected-(E13-Pad6)") (class "Default")
      (node (ref "E13") (pin "6") (pinfunction "6_6") (pintype "bidirectional"))
    )
    (net (code "160") (name "unconnected-(E14-Pad3)") (class "Default")
      (node (ref "E14") (pin "3") (pinfunction "3_3") (pintype "bidirectional"))
    )
    (net (code "161") (name "unconnected-(E14-Pad6)") (class "Default")
      (node (ref "E14") (pin "6") (pinfunction "6_6") (pintype "bidirectional"))
    )
    (net (code "162") (name "unconnected-(E15-Pad3)") (class "Default")
      (node (ref "E15") (pin "3") (pinfunction "3_3") (pintype "bidirectional"))
    )
    (net (code "163") (name "unconnected-(E15-Pad6)") (class "Default")
      (node (ref "E15") (pin "6") (pinfunction "6_6") (pintype "bidirectional"))
    )
    (net (code "164") (name "unconnected-(E16-Pad3)") (class "Default")
      (node (ref "E16") (pin "3") (pinfunction "3_3") (pintype "bidirectional"))
    )
    (net (code "165") (name "unconnected-(E16-Pad6)") (class "Default")
      (node (ref "E16") (pin "6") (pinfunction "6_6") (pintype "bidirectional"))
    )
    (net (code "166") (name "unconnected-(E17-Pad3)") (class "Default")
      (node (ref "E17") (pin "3") (pinfunction "3_3") (pintype "bidirectional"))
    )
    (net (code "167") (name "unconnected-(E17-Pad6)") (class "Default")
      (node (ref "E17") (pin "6") (pinfunction "6_6") (pintype "bidirectional"))
    )
    (net (code "168") (name "unconnected-(E18-Pad3)") (class "Default")
      (node (ref "E18") (pin "3") (pinfunction "3_3") (pintype "bidirectional"))
    )
    (net (code "169") (name "unconnected-(E18-Pad6)") (class "Default")
      (node (ref "E18") (pin "6") (pinfunction "6_6") (pintype "bidirectional"))
    )
    (net (code "170") (name "unconnected-(E19-Pad3)") (class "Default")
      (node (ref "E19") (pin "3") (pinfunction "3_3") (pintype "bidirectional"))
    )
    (net (code "171") (name "unconnected-(E19-Pad6)") (class "Default")
      (node (ref "E19") (pin "6") (pinfunction "6_6") (pintype "bidirectional"))
    )
    (net (code "172") (name "unconnected-(E20-Pad3)") (class "Default")
      (node (ref "E20") (pin "3") (pinfunction "3_3") (pintype "bidirectional"))
    )
    (net (code "173") (name "unconnected-(E20-Pad6)") (class "Default")
      (node (ref "E20") (pin "6") (pinfunction "6_6") (pintype "bidirectional"))
    )
    (net (code "174") (name "unconnected-(E21-Pad3)") (class "Default")
      (node (ref "E21") (pin "3") (pinfunction "3_3") (pintype "bidirectional"))
    )
    (net (code "175") (name "unconnected-(E21-Pad6)") (class "Default")
      (node (ref "E21") (pin "6") (pinfunction "6_6") (pintype "bidirectional"))
    )
    (net (code "176") (name "unconnected-(E22-Pad3)") (class "Default")
      (node (ref "E22") (pin "3") (pinfunction "3_3") (pintype "bidirectional"))
    )
    (net (code "177") (name "unconnected-(E22-Pad6)") (class "Default")
      (node (ref "E22") (pin "6") (pinfunction "6_6") (pintype "bidirectional"))
    )
    (net (code "178") (name "unconnected-(J1-SBU1-PadA8)") (class "Default")
      (node (ref "J1") (pin "A8") (pinfunction "SBU1_A8") (pintype "bidirectional"))
    )
    (net (code "179") (name "unconnected-(J1-SBU2-PadB8)") (class "Default")
      (node (ref "J1") (pin "B8") (pinfunction "SBU2_B8") (pintype "bidirectional"))
    )
    (net (code "180") (name "unconnected-(J2-SBU1-PadA8)") (class "Default")
      (node (ref "J2") (pin "A8") (pinfunction "SBU1_A8") (pintype "bidirectional"))
    )
    (net (code "181") (name "unconnected-(J2-SBU2-PadB8)") (class "Default")
      (node (ref "J2") (pin "B8") (pinfunction "SBU2_B8") (pintype "bidirectional"))
    )
    (net (code "182") (name "unconnected-(J3-SBU1-PadA8)") (class "Default")
      (node (ref "J3") (pin "A8") (pinfunction "SBU1_A8") (pintype "bidirectional"))
    )
    (net (code "183") (name "unconnected-(J3-SBU2-PadB8)") (class "Default")
      (node (ref "J3") (pin "B8") (pinfunction "SBU2_B8") (pintype "bidirectional"))
    )
    (net (code "184") (name "unconnected-(J4-SBU1-PadA8)") (class "Default")
      (node (ref "J4") (pin "A8") (pinfunction "SBU1_A8") (pintype "bidirectional"))
    )
    (net (code "185") (name "unconnected-(J4-SBU2-PadB8)") (class "Default")
      (node (ref "J4") (pin "B8") (pinfunction "SBU2_B8") (pintype "bidirectional"))
    )
    (net (code "186") (name "unconnected-(J5-SBU1-PadA8)") (class "Default")
      (node (ref "J5") (pin "A8") (pinfunction "SBU1_A8") (pintype "bidirectional"))
    )
    (net (code "187") (name "unconnected-(J5-SBU2-PadB8)") (class "Default")
      (node (ref "J5") (pin "B8") (pinfunction "SBU2_B8") (pintype "bidirectional"))
    )
    (net (code "188") (name "unconnected-(J6-SBU1-PadA8)") (class "Default")
      (node (ref "J6") (pin "A8") (pinfunction "SBU1_A8") (pintype "bidirectional"))
    )
    (net (code "189") (name "unconnected-(J6-SBU2-PadB8)") (class "Default")
      (node (ref "J6") (pin "B8") (pinfunction "SBU2_B8") (pintype "bidirectional"))
    )
    (net (code "190") (name "unconnected-(J7-SBU1-PadA8)") (class "Default")
      (node (ref "J7") (pin "A8") (pinfunction "SBU1_A8") (pintype "bidirectional"))
    )
    (net (code "191") (name "unconnected-(J7-SBU2-PadB8)") (class "Default")
      (node (ref "J7") (pin "B8") (pinfunction "SBU2_B8") (pintype "bidirectional"))
    )
    (net (code "192") (name "unconnected-(J8-SBU1-PadA8)") (class "Default")
      (node (ref "J8") (pin "A8") (pinfunction "SBU1_A8") (pintype "bidirectional"))
    )
    (net (code "193") (name "unconnected-(J8-SBU2-PadB8)") (class "Default")
      (node (ref "J8") (pin "B8") (pinfunction "SBU2_B8") (pintype "bidirectional"))
    )
    (net (code "194") (name "unconnected-(J9-SBU1-PadA8)") (class "Default")
      (node (ref "J9") (pin "A8") (pinfunction "SBU1_A8") (pintype "bidirectional"))
    )
    (net (code "195") (name "unconnected-(J9-SBU2-PadB8)") (class "Default")
      (node (ref "J9") (pin "B8") (pinfunction "SBU2_B8") (pintype "bidirectional"))
    )
    (net (code "196") (name "unconnected-(J10-SBU1-PadA8)") (class "Default")
      (node (ref "J10") (pin "A8") (pinfunction "SBU1_A8") (pintype "bidirectional"))
    )
    (net (code "197") (name "unconnected-(J10-SBU2-PadB8)") (class "Default")
      (node (ref "J10") (pin "B8") (pinfunction "SBU2_B8") (pintype "bidirectional"))
    )
    (net (code "198") (name "unconnected-(J11-SBU1-PadA8)") (class "Default")
      (node (ref "J11") (pin "A8") (pinfunction "SBU1_A8") (pintype "bidirectional"))
    )
    (net (code "199") (name "unconnected-(J11-SBU2-PadB8)") (class "Default")
      (node (ref "J11") (pin "B8") (pinfunction "SBU2_B8") (pintype "bidirectional"))
    )
    (net (code "200") (name "unconnected-(J12-SBU1-PadA8)") (class "Default")
      (node (ref "J12") (pin "A8") (pinfunction "SBU1_A8") (pintype "bidirectional"))
    )
    (net (code "201") (name "unconnected-(J12-SBU2-PadB8)") (class "Default")
      (node (ref "J12") (pin "B8") (pinfunction "SBU2_B8") (pintype "bidirectional"))
    )
    (net (code "202") (name "unconnected-(J13-SBU1-PadA8)") (class "Default")
      (node (ref "J13") (pin "A8") (pinfunction "SBU1_A8") (pintype "bidirectional"))
    )
    (net (code "203") (name "unconnected-(J13-SBU2-PadB8)") (class "Default")
      (node (ref "J13") (pin "B8") (pinfunction "SBU2_B8") (pintype "bidirectional"))
    )
    (net (code "204") (name "unconnected-(J14-SBU1-PadA8)") (class "Default")
      (node (ref "J14") (pin "A8") (pinfunction "SBU1_A8") (pintype "bidirectional"))
    )
    (net (code "205") (name "unconnected-(J14-SBU2-PadB8)") (class "Default")
      (node (ref "J14") (pin "B8") (pinfunction "SBU2_B8") (pintype "bidirectional"))
    )
    (net (code "206") (name "unconnected-(J15-SBU1-PadA8)") (class "Default")
      (node (ref "J15") (pin "A8") (pinfunction "SBU1_A8") (pintype "bidirectional"))
    )
    (net (code "207") (name "unconnected-(J15-SBU2-PadB8)") (class "Default")
      (node (ref "J15") (pin "B8") (pinfunction "SBU2_B8") (pintype "bidirectional"))
    )
    (net (code "208") (name "unconnected-(J16-SBU1-PadA8)") (class "Default")
      (node (ref "J16") (pin "A8") (pinfunction "SBU1_A8") (pintype "bidirectional"))
    )
    (net (code "209") (name "unconnected-(J16-SBU2-PadB8)") (class "Default")
      (node (ref "J16") (pin "B8") (pinfunction "SBU2_B8") (pintype "bidirectional"))
    )
    (net (code "210") (name "unconnected-(J17-SBU1-PadA8)") (class "Default")
      (node (ref "J17") (pin "A8") (pinfunction "SBU1_A8") (pintype "bidirectional"))
    )
    (net (code "211") (name "unconnected-(J17-SBU2-PadB8)") (class "Default")
      (node (ref "J17") (pin "B8") (pinfunction "SBU2_B8") (pintype "bidirectional"))
    )
    (net (code "212") (name "unconnected-(J18-SBU1-PadA8)") (class "Default")
      (node (ref "J18") (pin "A8") (pinfunction "SBU1_A8") (pintype "bidirectional"))
    )
    (net (code "213") (name "unconnected-(J18-SBU2-PadB8)") (class "Default")
      (node (ref "J18") (pin "B8") (pinfunction "SBU2_B8") (pintype "bidirectional"))
    )
    (net (code "214") (name "unconnected-(J19-SBU1-PadA8)") (class "Default")
      (node (ref "J19") (pin "A8") (pinfunction "SBU1_A8") (pintype "bidirectional"))
    )
    (net (code "215") (name "unconnected-(J19-SBU2-PadB8)") (class "Default")
      (node (ref "J19") (pin "B8") (pinfunction "SBU2_B8") (pintype "bidirectional"))
    )
    (net (code "216") (name "unconnected-(J20-SBU1-PadA8)") (class "Default")
      (node (ref "J20") (pin "A8") (pinfunction "SBU1_A8") (pintype "bidirectional"))
    )
    (net (code "217") (name "unconnected-(J20-SBU2-PadB8)") (class "Default")
      (node (ref "J20") (pin "B8") (pinfunction "SBU2_B8") (pintype "bidirectional"))
    )
    (net (code "218") (name "unconnected-(J21-SBU1-PadA8)") (class "Default")
      (node (ref "J21") (pin "A8") (pinfunction "SBU1_A8") (pintype "bidirectional"))
    )
    (net (code "219") (name "unconnected-(J21-SBU2-PadB8)") (class "Default")
      (node (ref "J21") (pin "B8") (pinfunction "SBU2_B8") (pintype "bidirectional"))
    )
    (net (code "220") (name "unconnected-(J26-SBU1-PadA8)") (class "Default")
      (node (ref "J26") (pin "A8") (pinfunction "SBU1_A8") (pintype "bidirectional"))
    )
    (net (code "221") (name "unconnected-(J26-SBU2-PadB8)") (class "Default")
      (node (ref "J26") (pin "B8") (pinfunction "SBU2_B8") (pintype "bidirectional"))
    )
  )
)
